# main_board.net
KiCad netlist of a schematic drawn in EAGLE
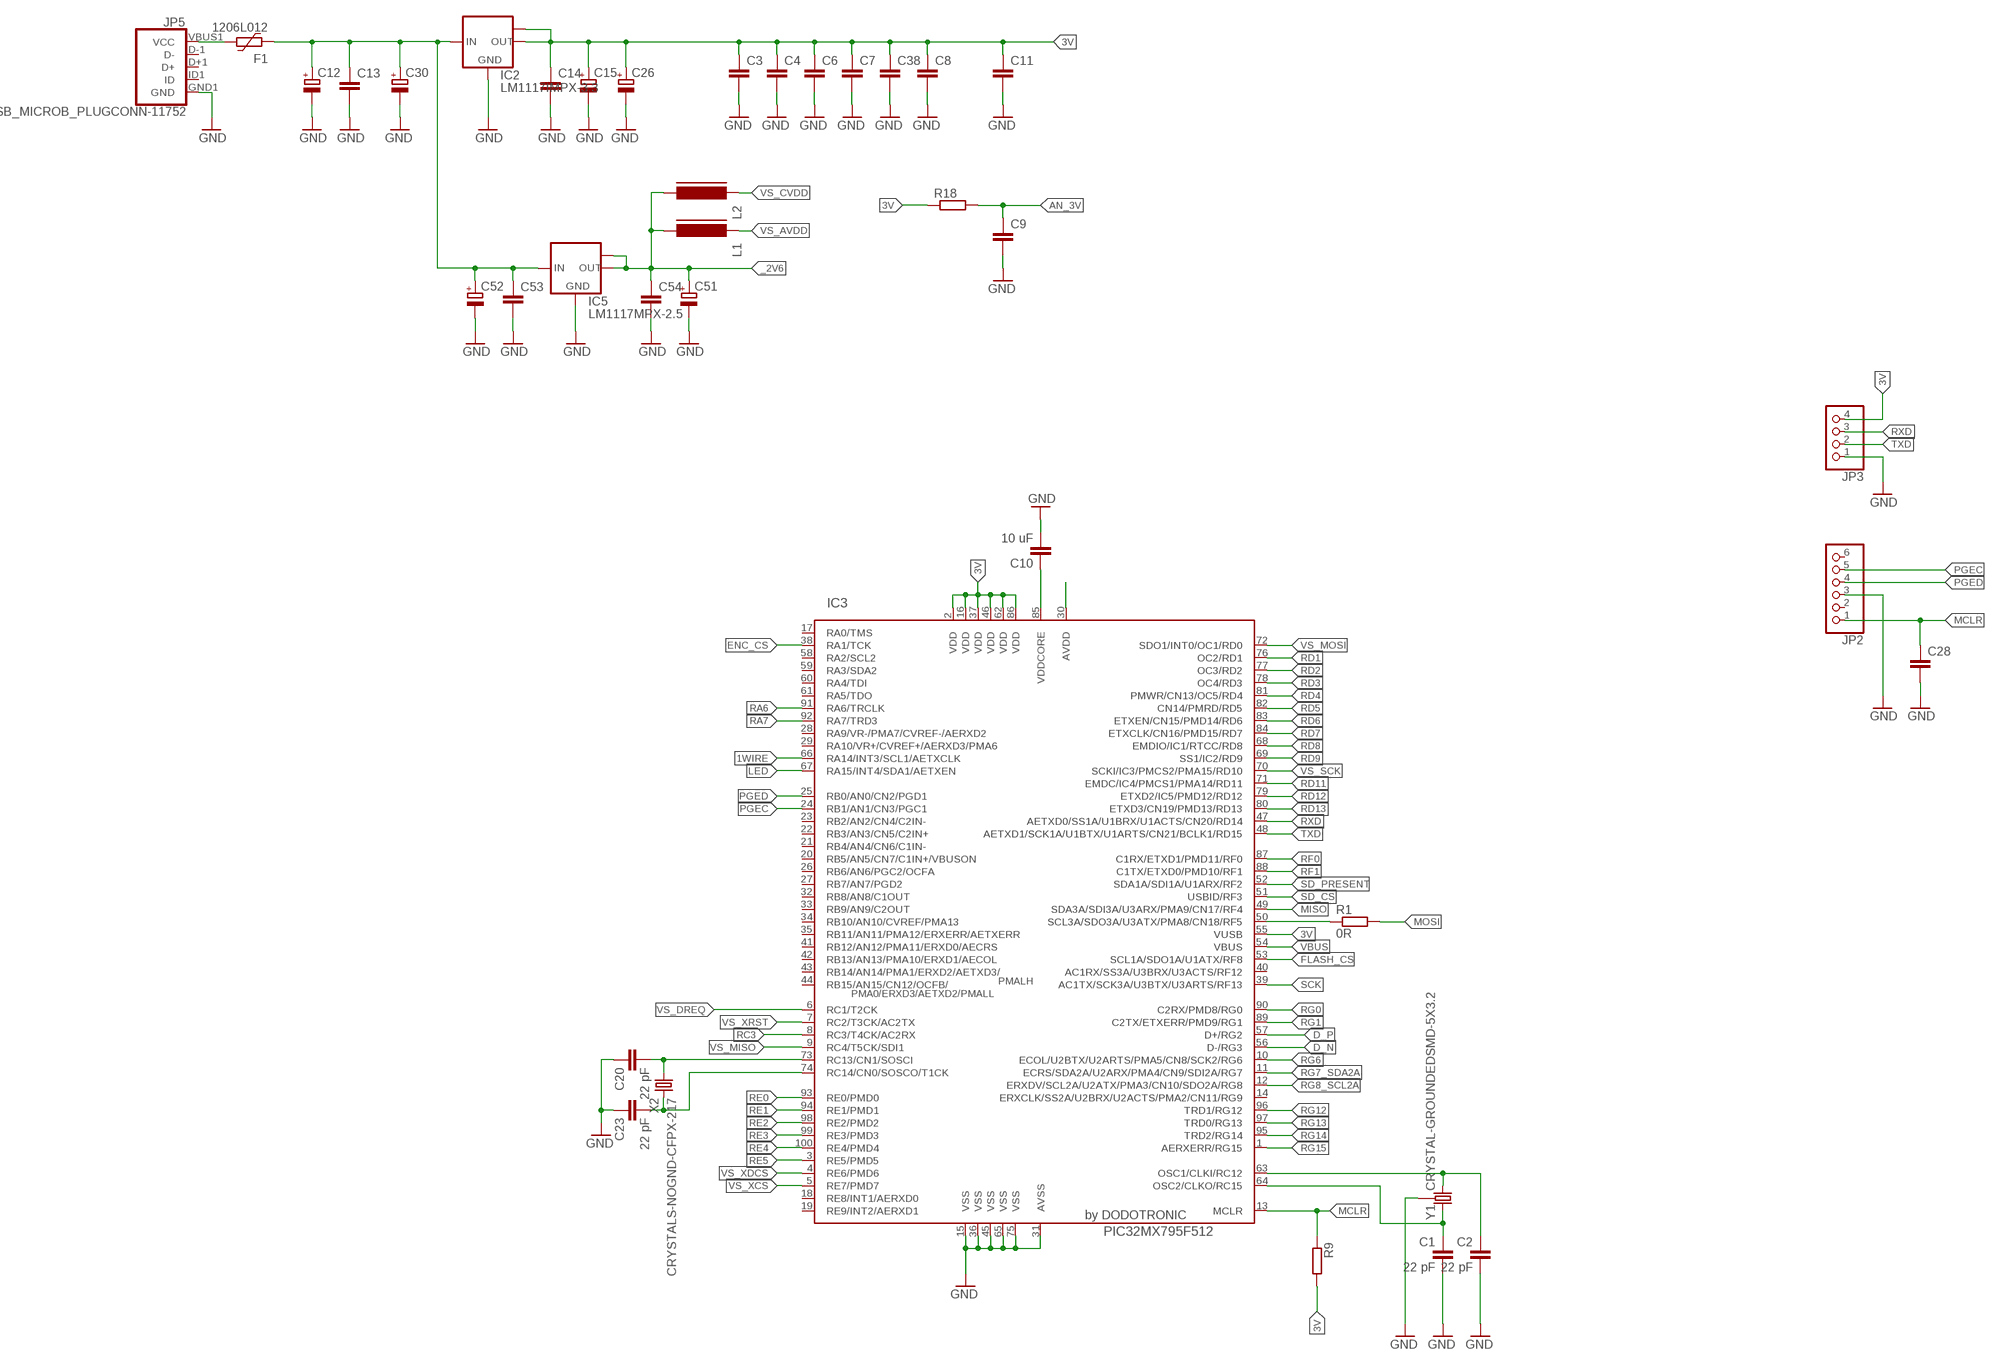
[diagram p0: schematic, sheet 1, part 1 of 3]
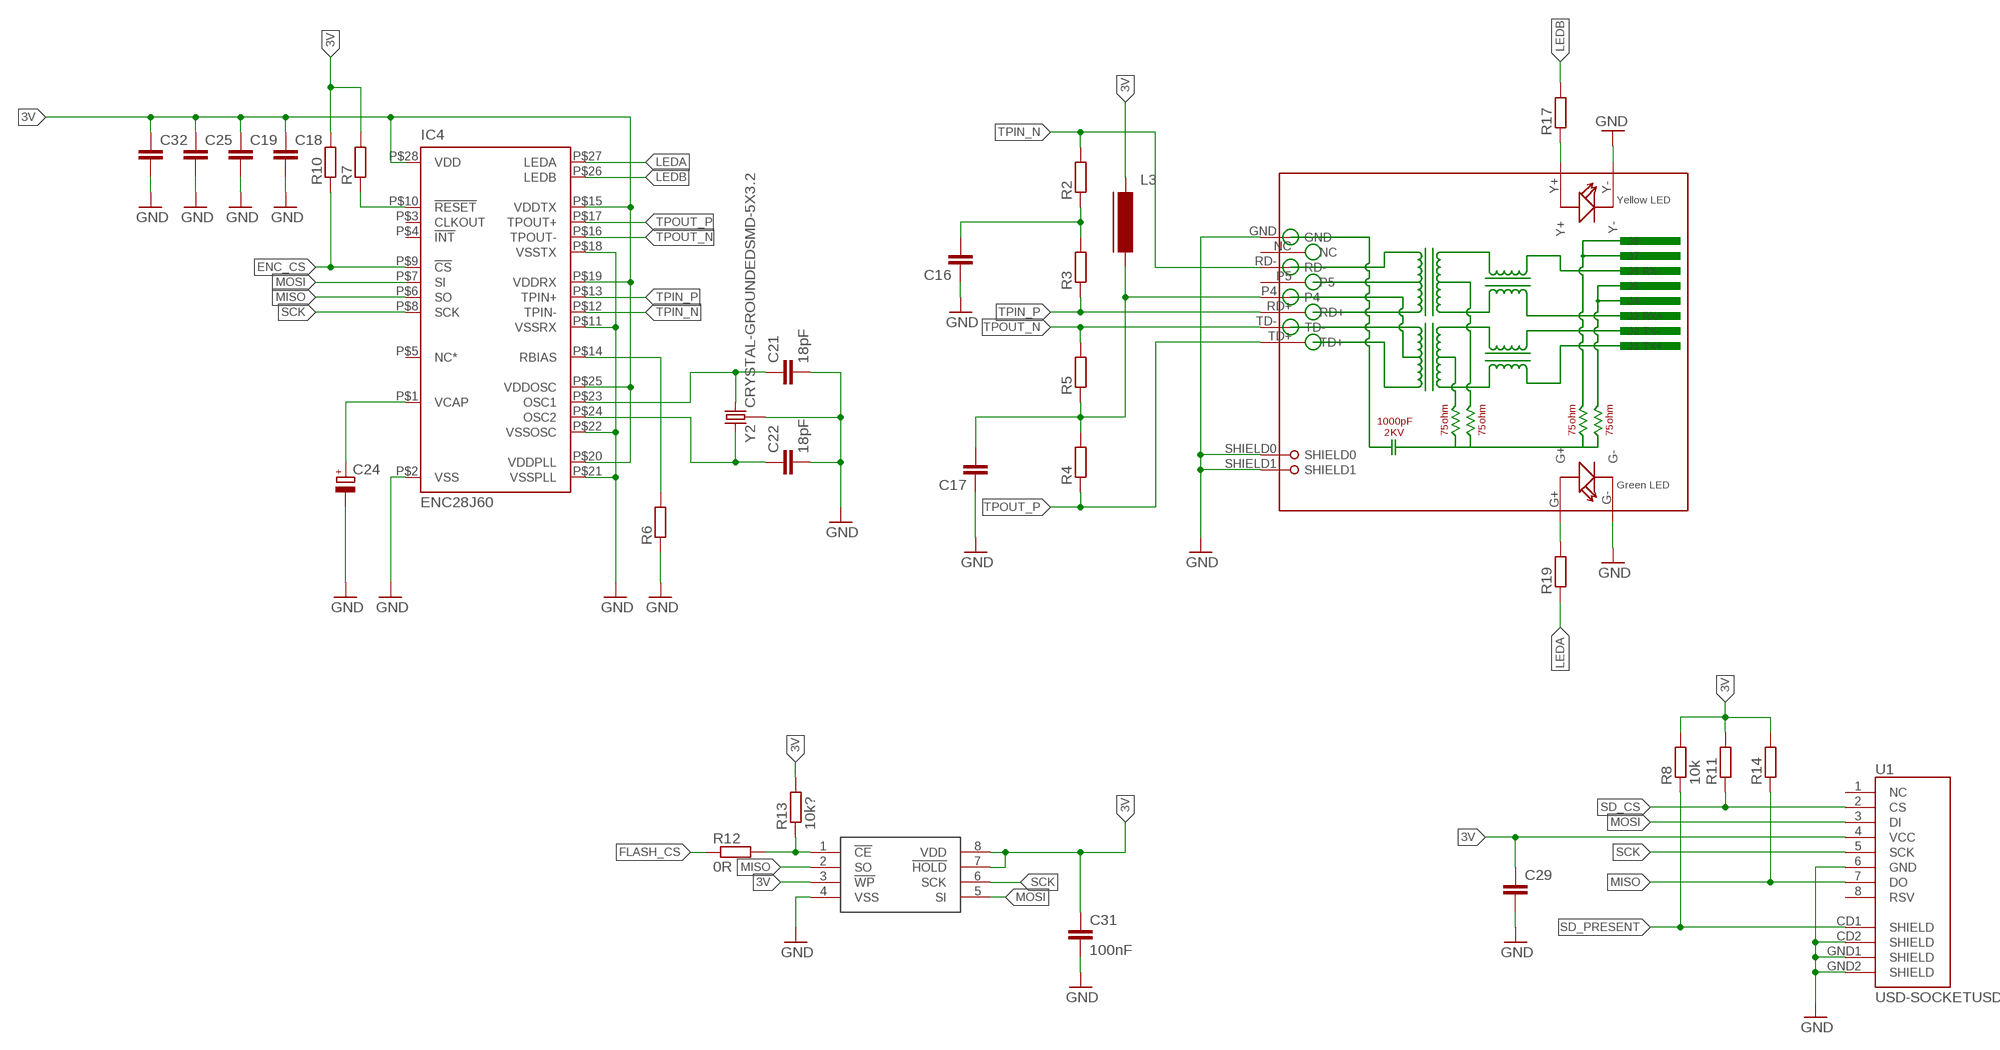
[diagram p1: schematic, sheet 1, part 2 of 3]
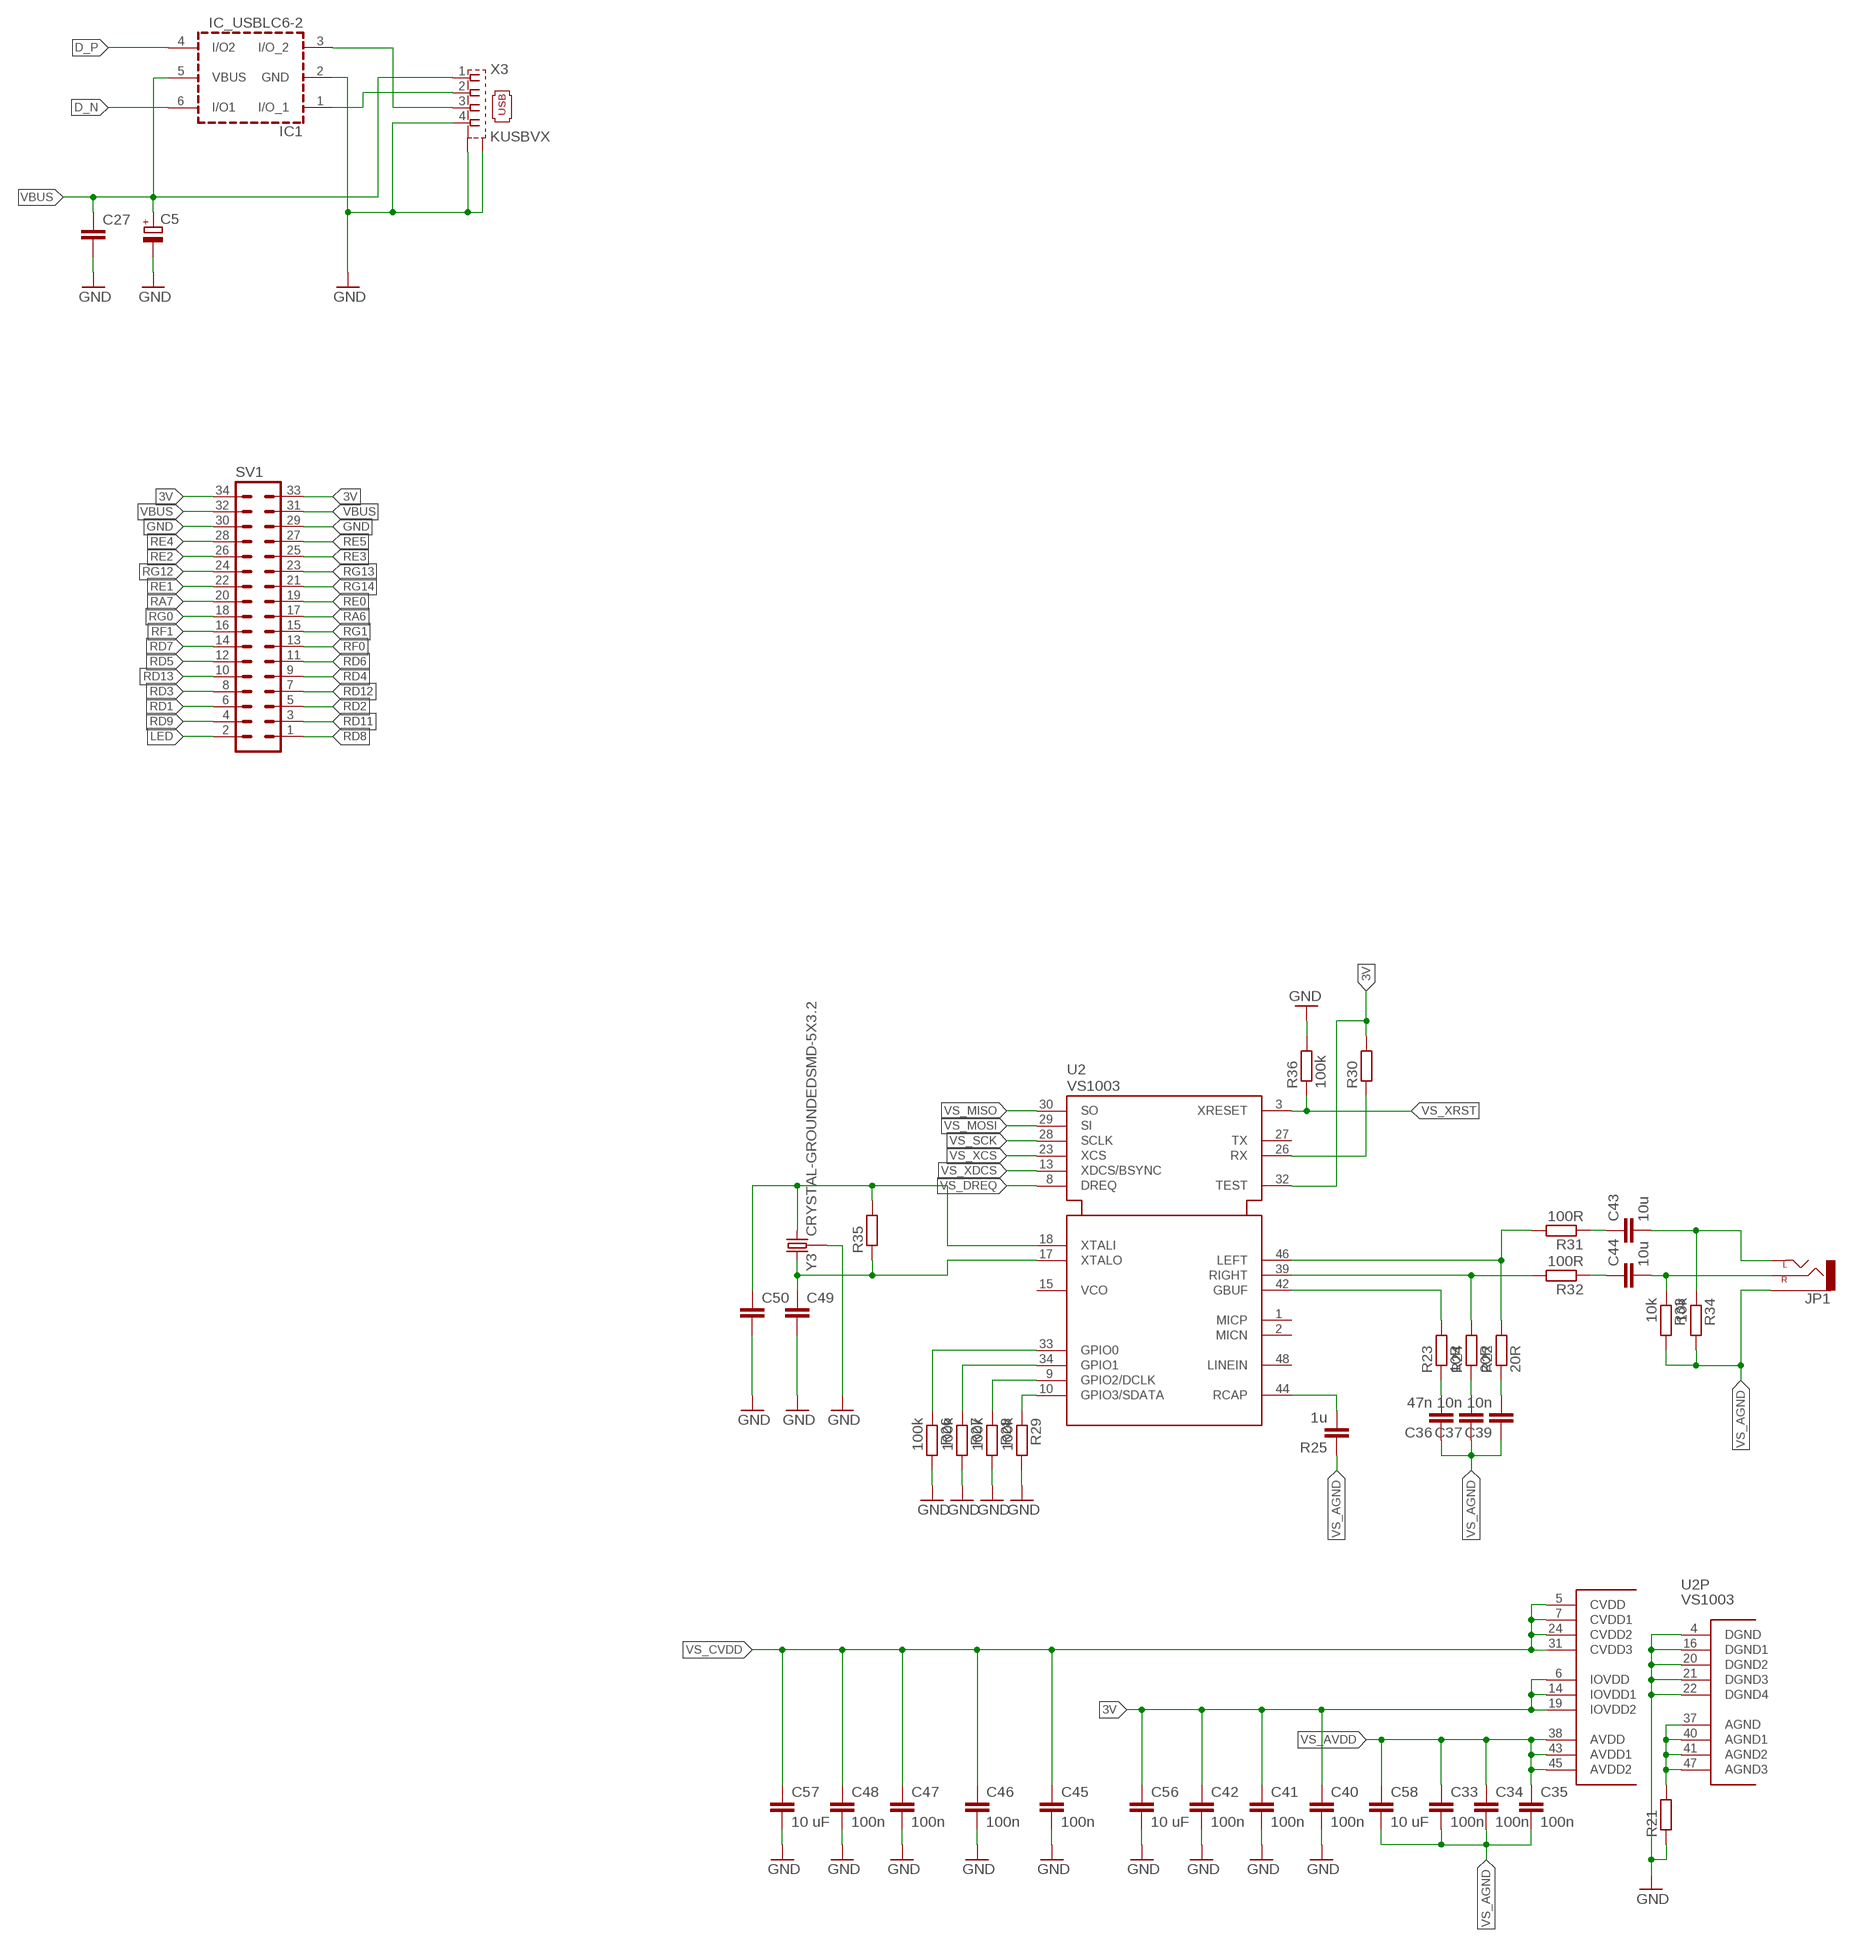
[diagram p2: schematic, sheet 1, part 3 of 3]

(export (version "E")
  (design (tool "Eeschema 10.0.6"))
  (components
    (comp (ref "C1")
      (value "22 pF")
      (footprint "eagle-import:C0603")
      (libsource (lib "eagle-import") (part "C-EUC0603"))
    )
    (comp (ref "C2")
      (value "22 pF")
      (footprint "eagle-import:C0603")
      (libsource (lib "eagle-import") (part "C-EUC0603"))
    )
    (comp (ref "C3")
      (value "C-EUC0402")
      (footprint "eagle-import:C0402")
      (libsource (lib "eagle-import") (part "C-EUC0402"))
    )
    (comp (ref "C4")
      (value "C-EUC0402")
      (footprint "eagle-import:C0402")
      (libsource (lib "eagle-import") (part "C-EUC0402"))
    )
    (comp (ref "C5")
      (value "CPOL-EUSMCA")
      (footprint "eagle-import:SMC_A")
      (libsource (lib "eagle-import") (part "CPOL-EUSMCA"))
    )
    (comp (ref "C6")
      (value "C-EUC0402")
      (footprint "eagle-import:C0402")
      (libsource (lib "eagle-import") (part "C-EUC0402"))
    )
    (comp (ref "C7")
      (value "C-EUC0402")
      (footprint "eagle-import:C0402")
      (libsource (lib "eagle-import") (part "C-EUC0402"))
    )
    (comp (ref "C8")
      (value "C-EUC0402")
      (footprint "eagle-import:C0402")
      (libsource (lib "eagle-import") (part "C-EUC0402"))
    )
    (comp (ref "C9")
      (value "C-EUC0402")
      (footprint "eagle-import:C0402")
      (libsource (lib "eagle-import") (part "C-EUC0402"))
    )
    (comp (ref "C10")
      (value "10 uF")
      (footprint "eagle-import:C0603")
      (libsource (lib "eagle-import") (part "C-EUC0603"))
    )
    (comp (ref "C11")
      (value "C-EUC0402")
      (footprint "eagle-import:C0402")
      (libsource (lib "eagle-import") (part "C-EUC0402"))
    )
    (comp (ref "C12")
      (value "CPOL-EUSMCB")
      (footprint "eagle-import:SMC_B")
      (libsource (lib "eagle-import") (part "CPOL-EUSMCB"))
    )
    (comp (ref "C13")
      (value "C-EUC0603")
      (footprint "eagle-import:C0603")
      (libsource (lib "eagle-import") (part "C-EUC0603"))
    )
    (comp (ref "C14")
      (value "C-EUC0603")
      (footprint "eagle-import:C0603")
      (libsource (lib "eagle-import") (part "C-EUC0603"))
    )
    (comp (ref "C15")
      (value "CPOL-EUSMCB")
      (footprint "eagle-import:SMC_B")
      (libsource (lib "eagle-import") (part "CPOL-EUSMCB"))
    )
    (comp (ref "C16")
      (value "C-EUC0603")
      (footprint "eagle-import:C0603")
      (libsource (lib "eagle-import") (part "C-EUC0603"))
    )
    (comp (ref "C17")
      (value "C-EUC0603")
      (footprint "eagle-import:C0603")
      (libsource (lib "eagle-import") (part "C-EUC0603"))
    )
    (comp (ref "C18")
      (value "C-EUC0402")
      (footprint "eagle-import:C0402")
      (libsource (lib "eagle-import") (part "C-EUC0402"))
    )
    (comp (ref "C19")
      (value "C-EUC0603")
      (footprint "eagle-import:C0603")
      (libsource (lib "eagle-import") (part "C-EUC0603"))
    )
    (comp (ref "C20")
      (value "22 pF")
      (footprint "eagle-import:C0603")
      (libsource (lib "eagle-import") (part "C-EUC0603"))
    )
    (comp (ref "C21")
      (value "18pF")
      (footprint "eagle-import:C0603")
      (libsource (lib "eagle-import") (part "C-EUC0603"))
    )
    (comp (ref "C22")
      (value "18pF")
      (footprint "eagle-import:C0603")
      (libsource (lib "eagle-import") (part "C-EUC0603"))
    )
    (comp (ref "C23")
      (value "22 pF")
      (footprint "eagle-import:C0603")
      (libsource (lib "eagle-import") (part "C-EUC0603"))
    )
    (comp (ref "C24")
      (value "CPOL-EUSMCA")
      (footprint "eagle-import:SMC_A")
      (libsource (lib "eagle-import") (part "CPOL-EUSMCA"))
    )
    (comp (ref "C25")
      (value "C-EUC0603")
      (footprint "eagle-import:C0603")
      (libsource (lib "eagle-import") (part "C-EUC0603"))
    )
    (comp (ref "C26")
      (value "CPOL-EUSMCA")
      (footprint "eagle-import:SMC_A")
      (libsource (lib "eagle-import") (part "CPOL-EUSMCA"))
    )
    (comp (ref "C27")
      (value "C-EUC0603")
      (footprint "eagle-import:C0603")
      (libsource (lib "eagle-import") (part "C-EUC0603"))
    )
    (comp (ref "C28")
      (value "C-EUC0603")
      (footprint "eagle-import:C0603")
      (libsource (lib "eagle-import") (part "C-EUC0603"))
    )
    (comp (ref "C29")
      (value "C-EUC0603")
      (footprint "eagle-import:C0603")
      (libsource (lib "eagle-import") (part "C-EUC0603"))
    )
    (comp (ref "C30")
      (value "CPOL-EUSMCA")
      (footprint "eagle-import:SMC_A")
      (libsource (lib "eagle-import") (part "CPOL-EUSMCA"))
    )
    (comp (ref "C31")
      (value "100nF")
      (footprint "eagle-import:C0603")
      (libsource (lib "eagle-import") (part "C-EUC0603"))
    )
    (comp (ref "C32")
      (value "C-EUC0402")
      (footprint "eagle-import:C0402")
      (libsource (lib "eagle-import") (part "C-EUC0402"))
    )
    (comp (ref "C33")
      (value "100n")
      (footprint "eagle-import:C0603")
      (libsource (lib "eagle-import") (part "C-EUC0603"))
    )
    (comp (ref "C34")
      (value "100n")
      (footprint "eagle-import:C0603")
      (libsource (lib "eagle-import") (part "C-EUC0603"))
    )
    (comp (ref "C35")
      (value "100n")
      (footprint "eagle-import:C0603")
      (libsource (lib "eagle-import") (part "C-EUC0603"))
    )
    (comp (ref "C36")
      (value "47n")
      (footprint "eagle-import:C0603")
      (libsource (lib "eagle-import") (part "C-EUC0603"))
    )
    (comp (ref "C37")
      (value "10n")
      (footprint "eagle-import:C0603")
      (libsource (lib "eagle-import") (part "C-EUC0603"))
    )
    (comp (ref "C38")
      (value "C-EUC0402")
      (footprint "eagle-import:C0402")
      (libsource (lib "eagle-import") (part "C-EUC0402"))
    )
    (comp (ref "C39")
      (value "10n")
      (footprint "eagle-import:C0603")
      (libsource (lib "eagle-import") (part "C-EUC0603"))
    )
    (comp (ref "C40")
      (value "100n")
      (footprint "eagle-import:C0402")
      (libsource (lib "eagle-import") (part "C-EUC0402"))
    )
    (comp (ref "C41")
      (value "100n")
      (footprint "eagle-import:C0402")
      (libsource (lib "eagle-import") (part "C-EUC0402"))
    )
    (comp (ref "C42")
      (value "100n")
      (footprint "eagle-import:C0402")
      (libsource (lib "eagle-import") (part "C-EUC0402"))
    )
    (comp (ref "C43")
      (value "10u")
      (footprint "eagle-import:C0603")
      (libsource (lib "eagle-import") (part "C-EUC0603"))
    )
    (comp (ref "C44")
      (value "10u")
      (footprint "eagle-import:C0603")
      (libsource (lib "eagle-import") (part "C-EUC0603"))
    )
    (comp (ref "C45")
      (value "100n")
      (footprint "eagle-import:C0402")
      (libsource (lib "eagle-import") (part "C-EUC0402"))
    )
    (comp (ref "C46")
      (value "100n")
      (footprint "eagle-import:C0603")
      (libsource (lib "eagle-import") (part "C-EUC0603"))
    )
    (comp (ref "C47")
      (value "100n")
      (footprint "eagle-import:C0603")
      (libsource (lib "eagle-import") (part "C-EUC0603"))
    )
    (comp (ref "C48")
      (value "100n")
      (footprint "eagle-import:C0603")
      (libsource (lib "eagle-import") (part "C-EUC0603"))
    )
    (comp (ref "C49")
      (value "C-EUC0603")
      (footprint "eagle-import:C0603")
      (libsource (lib "eagle-import") (part "C-EUC0603"))
    )
    (comp (ref "C50")
      (value "C-EUC0603")
      (footprint "eagle-import:C0603")
      (libsource (lib "eagle-import") (part "C-EUC0603"))
    )
    (comp (ref "C51")
      (value "CPOL-EUSMCB")
      (footprint "eagle-import:SMC_B")
      (libsource (lib "eagle-import") (part "CPOL-EUSMCB"))
    )
    (comp (ref "C52")
      (value "CPOL-EUSMCB")
      (footprint "eagle-import:SMC_B")
      (libsource (lib "eagle-import") (part "CPOL-EUSMCB"))
    )
    (comp (ref "C53")
      (value "C-EUC1206")
      (footprint "eagle-import:C1206")
      (libsource (lib "eagle-import") (part "C-EUC1206"))
    )
    (comp (ref "C54")
      (value "C-EUC1206")
      (footprint "eagle-import:C1206")
      (libsource (lib "eagle-import") (part "C-EUC1206"))
    )
    (comp (ref "C56")
      (value "10 uF")
      (footprint "eagle-import:C0603")
      (libsource (lib "eagle-import") (part "C-EUC0603"))
    )
    (comp (ref "C57")
      (value "10 uF")
      (footprint "eagle-import:C0603")
      (libsource (lib "eagle-import") (part "C-EUC0603"))
    )
    (comp (ref "C58")
      (value "10 uF")
      (footprint "eagle-import:C0603")
      (libsource (lib "eagle-import") (part "C-EUC0603"))
    )
    (comp (ref "F1")
      (value "1206L012")
      (footprint "eagle-import:1206L")
      (fields (field (name "MF") "Littelfuse"))
      (libsource (lib "eagle-import") (part "?1206L012"))
    )
    (comp (ref "IC1")
      (value "IC_USBLC6-2")
      (footprint "eagle-import:SOT-23-6L")
      (libsource (lib "eagle-import") (part "IC_USBLC6-2"))
    )
    (comp (ref "IC2")
      (value "LM1117IMPX-3.3")
      (footprint "eagle-import:SOT223")
      (libsource (lib "eagle-import") (part "LM1117IMPX-3.3"))
    )
    (comp (ref "IC3")
      (value "PIC32MX795F512")
      (footprint "eagle-import:TQFP100_12X12")
      (libsource (lib "eagle-import") (part "PIC32MX795F512"))
    )
    (comp (ref "IC4")
      (value "ENC28J60")
      (footprint "eagle-import:TSSOP28W")
      (libsource (lib "eagle-import") (part "ENC28J60"))
    )
    (comp (ref "IC5")
      (value "LM1117MPX-2.5")
      (footprint "eagle-import:SOT223")
      (libsource (lib "eagle-import") (part "LM1117MPX-2.5"))
    )
    (comp (ref "JP1")
      (value "AUDIO-JACKAUDIO_JACK2")
      (footprint "eagle-import:AUDIO-JACK2")
      (libsource (lib "eagle-import") (part "AUDIO-JACKAUDIO_JACK2"))
    )
    (comp (ref "JP2")
      (value "PINHD-1X6")
      (footprint "eagle-import:1X06")
      (libsource (lib "eagle-import") (part "PINHD-1X6"))
    )
    (comp (ref "JP3")
      (value "PINHD-1X4")
      (footprint "eagle-import:1X04")
      (libsource (lib "eagle-import") (part "PINHD-1X4"))
    )
    (comp (ref "JP5")
      (value "USB_MICROB_PLUGCONN-11752")
      (footprint "eagle-import:USB-B-MICRO-SMD_V03")
      (libsource (lib "eagle-import") (part "USB_MICROB_PLUGCONN-11752"))
    )
    (comp (ref "L1")
      (value "FERRITE-0805")
      (footprint "eagle-import:FB805")
      (libsource (lib "eagle-import") (part "FERRITE-0805"))
    )
    (comp (ref "L2")
      (value "FERRITE-0805")
      (footprint "eagle-import:FB805")
      (libsource (lib "eagle-import") (part "FERRITE-0805"))
    )
    (comp (ref "L3")
      (value "FERRITE-0805")
      (footprint "eagle-import:FB805")
      (libsource (lib "eagle-import") (part "FERRITE-0805"))
    )
    (comp (ref "R1")
      (value "0R")
      (footprint "eagle-import:R0603")
      (libsource (lib "eagle-import") (part "R-EU_R0603"))
    )
    (comp (ref "R2")
      (value "R-EU_R0603")
      (footprint "eagle-import:R0603")
      (libsource (lib "eagle-import") (part "R-EU_R0603"))
    )
    (comp (ref "R3")
      (value "R-EU_R0603")
      (footprint "eagle-import:R0603")
      (libsource (lib "eagle-import") (part "R-EU_R0603"))
    )
    (comp (ref "R4")
      (value "R-EU_R0603")
      (footprint "eagle-import:R0603")
      (libsource (lib "eagle-import") (part "R-EU_R0603"))
    )
    (comp (ref "R5")
      (value "R-EU_R0603")
      (footprint "eagle-import:R0603")
      (libsource (lib "eagle-import") (part "R-EU_R0603"))
    )
    (comp (ref "R6")
      (value "R-EU_R0805")
      (footprint "eagle-import:R0805")
      (libsource (lib "eagle-import") (part "R-EU_R0805"))
    )
    (comp (ref "R7")
      (value "R-EU_R0402")
      (footprint "eagle-import:R0402")
      (libsource (lib "eagle-import") (part "R-EU_R0402"))
    )
    (comp (ref "R8")
      (value "10k")
      (footprint "eagle-import:R0603")
      (libsource (lib "eagle-import") (part "R-EU_R0603"))
    )
    (comp (ref "R9")
      (value "R-EU_R0603")
      (footprint "eagle-import:R0603")
      (libsource (lib "eagle-import") (part "R-EU_R0603"))
    )
    (comp (ref "R10")
      (value "R-EU_R0603")
      (footprint "eagle-import:R0603")
      (libsource (lib "eagle-import") (part "R-EU_R0603"))
    )
    (comp (ref "R11")
      (value "R-EU_R0603")
      (footprint "eagle-import:R0603")
      (libsource (lib "eagle-import") (part "R-EU_R0603"))
    )
    (comp (ref "R12")
      (value "0R")
      (footprint "eagle-import:R0603")
      (libsource (lib "eagle-import") (part "R-EU_R0603"))
    )
    (comp (ref "R13")
      (value "10k?")
      (footprint "eagle-import:R0603")
      (libsource (lib "eagle-import") (part "R-EU_R0603"))
    )
    (comp (ref "R14")
      (value "R-EU_R0603")
      (footprint "eagle-import:R0603")
      (libsource (lib "eagle-import") (part "R-EU_R0603"))
    )
    (comp (ref "R17")
      (value "R-EU_R1206")
      (footprint "eagle-import:R1206")
      (libsource (lib "eagle-import") (part "R-EU_R1206"))
    )
    (comp (ref "R18")
      (value "R-EU_R0805")
      (footprint "eagle-import:R0805")
      (libsource (lib "eagle-import") (part "R-EU_R0805"))
    )
    (comp (ref "R19")
      (value "R-EU_R1206")
      (footprint "eagle-import:R1206")
      (libsource (lib "eagle-import") (part "R-EU_R1206"))
    )
    (comp (ref "R21")
      (value "R-EU_R0603")
      (footprint "eagle-import:R0603")
      (libsource (lib "eagle-import") (part "R-EU_R0603"))
    )
    (comp (ref "R22")
      (value "20R")
      (footprint "eagle-import:R0603")
      (libsource (lib "eagle-import") (part "R-EU_R0603"))
    )
    (comp (ref "R23")
      (value "10R")
      (footprint "eagle-import:R0603")
      (libsource (lib "eagle-import") (part "R-EU_R0603"))
    )
    (comp (ref "R24")
      (value "20R")
      (footprint "eagle-import:R0603")
      (libsource (lib "eagle-import") (part "R-EU_R0603"))
    )
    (comp (ref "R25")
      (value "1u")
      (footprint "eagle-import:C0603")
      (libsource (lib "eagle-import") (part "C-EUC0603"))
    )
    (comp (ref "R26")
      (value "100k")
      (footprint "eagle-import:R0402")
      (libsource (lib "eagle-import") (part "R-EU_R0402"))
    )
    (comp (ref "R27")
      (value "100k")
      (footprint "eagle-import:R0402")
      (libsource (lib "eagle-import") (part "R-EU_R0402"))
    )
    (comp (ref "R28")
      (value "100k")
      (footprint "eagle-import:R0402")
      (libsource (lib "eagle-import") (part "R-EU_R0402"))
    )
    (comp (ref "R29")
      (value "100k")
      (footprint "eagle-import:R0402")
      (libsource (lib "eagle-import") (part "R-EU_R0402"))
    )
    (comp (ref "R30")
      (value "R-EU_0204/7")
      (footprint "eagle-import:0204_7")
      (libsource (lib "eagle-import") (part "R-EU_0204/7"))
    )
    (comp (ref "R31")
      (value "100R")
      (footprint "eagle-import:R0603")
      (libsource (lib "eagle-import") (part "R-EU_R0603"))
    )
    (comp (ref "R32")
      (value "100R")
      (footprint "eagle-import:R0603")
      (libsource (lib "eagle-import") (part "R-EU_R0603"))
    )
    (comp (ref "R33")
      (value "10k")
      (footprint "eagle-import:R0603")
      (libsource (lib "eagle-import") (part "R-EU_R0603"))
    )
    (comp (ref "R34")
      (value "10k")
      (footprint "eagle-import:R0603")
      (libsource (lib "eagle-import") (part "R-EU_R0603"))
    )
    (comp (ref "R35")
      (value "R-EU_R0603")
      (footprint "eagle-import:R0603")
      (libsource (lib "eagle-import") (part "R-EU_R0603"))
    )
    (comp (ref "R36")
      (value "100k")
      (footprint "eagle-import:R0603")
      (libsource (lib "eagle-import") (part "R-EU_R0603"))
    )
    (comp (ref "RJ1")
      (value "HR911105A")
      (footprint "eagle-import:HR911105A")
      (libsource (lib "eagle-import") (part "HR911105A"))
    )
    (comp (ref "SV1")
      (value "ML34L")
      (footprint "eagle-import:ML34L")
      (libsource (lib "eagle-import") (part "ML34L"))
    )
    (comp (ref "U$2")
      (value "SST25VF016BSO8M")
      (footprint "eagle-import:SO-08M")
      (libsource (lib "eagle-import") (part "SST25VF016BSO8M"))
    )
    (comp (ref "U1")
      (value "USD-SOCKETUSD")
      (footprint "eagle-import:USD-SOCKET-PP")
      (libsource (lib "eagle-import") (part "USD-SOCKETUSD"))
    )
    (comp (ref "U2")
      (value "VS1003")
      (footprint "eagle-import:LQFP48")
      (libsource (lib "eagle-import") (part "VS1003"))
    )
    (comp (ref "X2")
      (value "CRYSTALS-NOGND-CFPX-217")
      (footprint "eagle-import:3.2X1.5-2-PAD")
      (libsource (lib "eagle-import") (part "CRYSTALS-NOGND-CFPX-217"))
    )
    (comp (ref "X3")
      (value "KUSBVX")
      (footprint "eagle-import:KUSBVX")
      (libsource (lib "eagle-import") (part "KUSBVX"))
    )
    (comp (ref "Y1")
      (value "CRYSTAL-GROUNDEDSMD-5X3.2")
      (footprint "eagle-import:CRYSTAL-SMD-5X3.2-4PAD")
      (libsource (lib "eagle-import") (part "CRYSTAL-GROUNDEDSMD-5X3.2"))
    )
    (comp (ref "Y2")
      (value "CRYSTAL-GROUNDEDSMD-5X3.2")
      (footprint "eagle-import:CRYSTAL-SMD-5X3.2-4PAD")
      (libsource (lib "eagle-import") (part "CRYSTAL-GROUNDEDSMD-5X3.2"))
    )
    (comp (ref "Y3")
      (value "CRYSTAL-GROUNDEDSMD-5X3.2")
      (footprint "eagle-import:CRYSTAL-SMD-5X3.2-4PAD")
      (libsource (lib "eagle-import") (part "CRYSTAL-GROUNDEDSMD-5X3.2"))
    )
  )
  (nets
    (net (code "1") (name "1WIRE") (class "Default")
      (node (ref "IC3") (pin "66") (pinfunction "RA14/INT3/SCL1/AETXCLK_66") (pintype "bidirectional"))
    )
    (net (code "2") (name "3V") (class "Default")
      (node (ref "C11") (pin "1") (pinfunction "1_1") (pintype "passive"))
      (node (ref "C14") (pin "1") (pinfunction "1_1") (pintype "passive"))
      (node (ref "C15") (pin "+") (pinfunction "+_+") (pintype "passive"))
      (node (ref "C18") (pin "1") (pinfunction "1_1") (pintype "passive"))
      (node (ref "C19") (pin "1") (pinfunction "1_1") (pintype "passive"))
      (node (ref "C25") (pin "1") (pinfunction "1_1") (pintype "passive"))
      (node (ref "C26") (pin "+") (pinfunction "+_+") (pintype "passive"))
      (node (ref "C29") (pin "1") (pinfunction "1_1") (pintype "passive"))
      (node (ref "C3") (pin "1") (pinfunction "1_1") (pintype "passive"))
      (node (ref "C31") (pin "1") (pinfunction "1_1") (pintype "passive"))
      (node (ref "C32") (pin "1") (pinfunction "1_1") (pintype "passive"))
      (node (ref "C38") (pin "1") (pinfunction "1_1") (pintype "passive"))
      (node (ref "C4") (pin "1") (pinfunction "1_1") (pintype "passive"))
      (node (ref "C40") (pin "1") (pinfunction "1_1") (pintype "passive"))
      (node (ref "C41") (pin "1") (pinfunction "1_1") (pintype "passive"))
      (node (ref "C42") (pin "1") (pinfunction "1_1") (pintype "passive"))
      (node (ref "C56") (pin "1") (pinfunction "1_1") (pintype "passive"))
      (node (ref "C6") (pin "1") (pinfunction "1_1") (pintype "passive"))
      (node (ref "C7") (pin "1") (pinfunction "1_1") (pintype "passive"))
      (node (ref "C8") (pin "1") (pinfunction "1_1") (pintype "passive"))
      (node (ref "IC2") (pin "2") (pinfunction "OUT_2") (pintype "passive"))
      (node (ref "IC2") (pin "TAB") (pinfunction "OUT1_TAB") (pintype "passive"))
      (node (ref "IC3") (pin "16") (pinfunction "VDD_16") (pintype "power_in"))
      (node (ref "IC3") (pin "2") (pinfunction "VDD_2") (pintype "power_in"))
      (node (ref "IC3") (pin "37") (pinfunction "VDD_37") (pintype "power_in"))
      (node (ref "IC3") (pin "46") (pinfunction "VDD_46") (pintype "power_in"))
      (node (ref "IC3") (pin "55") (pinfunction "VUSB_55") (pintype "bidirectional"))
      (node (ref "IC3") (pin "62") (pinfunction "VDD_62") (pintype "power_in"))
      (node (ref "IC3") (pin "86") (pinfunction "VDD_86") (pintype "power_in"))
      (node (ref "IC4") (pin "P$15") (pinfunction "VDDTX_P$15") (pintype "input"))
      (node (ref "IC4") (pin "P$19") (pinfunction "VDDRX_P$19") (pintype "input"))
      (node (ref "IC4") (pin "P$20") (pinfunction "VDDPLL_P$20") (pintype "input"))
      (node (ref "IC4") (pin "P$25") (pinfunction "VDDOSC_P$25") (pintype "input"))
      (node (ref "IC4") (pin "P$28") (pinfunction "VDD_P$28") (pintype "input"))
      (node (ref "JP3") (pin "4") (pinfunction "4_4") (pintype "passive"))
      (node (ref "L3") (pin "1") (pinfunction "1_1") (pintype "passive"))
      (node (ref "R10") (pin "2") (pinfunction "2_2") (pintype "passive"))
      (node (ref "R11") (pin "2") (pinfunction "2_2") (pintype "passive"))
      (node (ref "R13") (pin "2") (pinfunction "2_2") (pintype "passive"))
      (node (ref "R14") (pin "2") (pinfunction "2_2") (pintype "passive"))
      (node (ref "R18") (pin "1") (pinfunction "1_1") (pintype "passive"))
      (node (ref "R30") (pin "2") (pinfunction "2_2") (pintype "passive"))
      (node (ref "R7") (pin "2") (pinfunction "2_2") (pintype "passive"))
      (node (ref "R8") (pin "2") (pinfunction "2_2") (pintype "passive"))
      (node (ref "R9") (pin "2") (pinfunction "2_2") (pintype "passive"))
      (node (ref "SV1") (pin "33") (pinfunction "33_33") (pintype "passive"))
      (node (ref "SV1") (pin "34") (pinfunction "34_34") (pintype "passive"))
      (node (ref "U$2") (pin "3") (pinfunction "~{WP}_3") (pintype "bidirectional"))
      (node (ref "U$2") (pin "7") (pinfunction "~{HOLD}_7") (pintype "bidirectional"))
      (node (ref "U$2") (pin "8") (pinfunction "VDD_8") (pintype "bidirectional"))
      (node (ref "U1") (pin "4") (pinfunction "VCC_4") (pintype "bidirectional"))
      (node (ref "U2") (pin "14") (pinfunction "IOVDD1_14") (pintype "power_in"))
      (node (ref "U2") (pin "19") (pinfunction "IOVDD2_19") (pintype "power_in"))
      (node (ref "U2") (pin "32") (pinfunction "TEST_32") (pintype "bidirectional"))
      (node (ref "U2") (pin "6") (pinfunction "IOVDD_6") (pintype "power_in"))
    )
    (net (code "3") (name "AN_3V") (class "Default")
      (node (ref "C9") (pin "1") (pinfunction "1_1") (pintype "passive"))
      (node (ref "IC3") (pin "30") (pinfunction "AVDD_30") (pintype "bidirectional"))
      (node (ref "R18") (pin "2") (pinfunction "2_2") (pintype "passive"))
    )
    (net (code "4") (name "D_N") (class "Default")
      (node (ref "IC1") (pin "6") (pinfunction "I/O1_6") (pintype "bidirectional"))
      (node (ref "IC3") (pin "56") (pinfunction "D-/RG3_56") (pintype "bidirectional"))
    )
    (net (code "5") (name "D_P") (class "Default")
      (node (ref "IC1") (pin "4") (pinfunction "I/O2_4") (pintype "bidirectional"))
      (node (ref "IC3") (pin "57") (pinfunction "D+/RG2_57") (pintype "bidirectional"))
    )
    (net (code "6") (name "ENC_CS") (class "Default")
      (node (ref "IC3") (pin "38") (pinfunction "RA1/TCK_38") (pintype "bidirectional"))
      (node (ref "IC4") (pin "P$9") (pinfunction "~{CS}_P$9") (pintype "input"))
      (node (ref "R10") (pin "1") (pinfunction "1_1") (pintype "passive"))
    )
    (net (code "7") (name "FLASH_CS") (class "Default")
      (node (ref "IC3") (pin "53") (pinfunction "SCL1A/SDO1A/U1ATX/RF8_53") (pintype "bidirectional"))
      (node (ref "R12") (pin "1") (pinfunction "1_1") (pintype "passive"))
    )
    (net (code "8") (name "GND") (class "Default")
      (node (ref "C1") (pin "2") (pinfunction "2_2") (pintype "passive"))
      (node (ref "C10") (pin "2") (pinfunction "2_2") (pintype "passive"))
      (node (ref "C11") (pin "2") (pinfunction "2_2") (pintype "passive"))
      (node (ref "C12") (pin "-") (pinfunction "-_-") (pintype "passive"))
      (node (ref "C13") (pin "2") (pinfunction "2_2") (pintype "passive"))
      (node (ref "C14") (pin "2") (pinfunction "2_2") (pintype "passive"))
      (node (ref "C15") (pin "-") (pinfunction "-_-") (pintype "passive"))
      (node (ref "C16") (pin "1") (pinfunction "1_1") (pintype "passive"))
      (node (ref "C17") (pin "1") (pinfunction "1_1") (pintype "passive"))
      (node (ref "C18") (pin "2") (pinfunction "2_2") (pintype "passive"))
      (node (ref "C19") (pin "2") (pinfunction "2_2") (pintype "passive"))
      (node (ref "C2") (pin "2") (pinfunction "2_2") (pintype "passive"))
      (node (ref "C20") (pin "1") (pinfunction "1_1") (pintype "passive"))
      (node (ref "C21") (pin "2") (pinfunction "2_2") (pintype "passive"))
      (node (ref "C22") (pin "2") (pinfunction "2_2") (pintype "passive"))
      (node (ref "C23") (pin "1") (pinfunction "1_1") (pintype "passive"))
      (node (ref "C24") (pin "-") (pinfunction "-_-") (pintype "passive"))
      (node (ref "C25") (pin "2") (pinfunction "2_2") (pintype "passive"))
      (node (ref "C26") (pin "-") (pinfunction "-_-") (pintype "passive"))
      (node (ref "C27") (pin "2") (pinfunction "2_2") (pintype "passive"))
      (node (ref "C28") (pin "2") (pinfunction "2_2") (pintype "passive"))
      (node (ref "C29") (pin "2") (pinfunction "2_2") (pintype "passive"))
      (node (ref "C3") (pin "2") (pinfunction "2_2") (pintype "passive"))
      (node (ref "C30") (pin "-") (pinfunction "-_-") (pintype "passive"))
      (node (ref "C31") (pin "2") (pinfunction "2_2") (pintype "passive"))
      (node (ref "C32") (pin "2") (pinfunction "2_2") (pintype "passive"))
      (node (ref "C38") (pin "2") (pinfunction "2_2") (pintype "passive"))
      (node (ref "C4") (pin "2") (pinfunction "2_2") (pintype "passive"))
      (node (ref "C40") (pin "2") (pinfunction "2_2") (pintype "passive"))
      (node (ref "C41") (pin "2") (pinfunction "2_2") (pintype "passive"))
      (node (ref "C42") (pin "2") (pinfunction "2_2") (pintype "passive"))
      (node (ref "C45") (pin "2") (pinfunction "2_2") (pintype "passive"))
      (node (ref "C46") (pin "2") (pinfunction "2_2") (pintype "passive"))
      (node (ref "C47") (pin "2") (pinfunction "2_2") (pintype "passive"))
      (node (ref "C48") (pin "2") (pinfunction "2_2") (pintype "passive"))
      (node (ref "C49") (pin "2") (pinfunction "2_2") (pintype "passive"))
      (node (ref "C5") (pin "-") (pinfunction "-_-") (pintype "passive"))
      (node (ref "C50") (pin "2") (pinfunction "2_2") (pintype "passive"))
      (node (ref "C51") (pin "-") (pinfunction "-_-") (pintype "passive"))
      (node (ref "C52") (pin "-") (pinfunction "-_-") (pintype "passive"))
      (node (ref "C53") (pin "2") (pinfunction "2_2") (pintype "passive"))
      (node (ref "C54") (pin "2") (pinfunction "2_2") (pintype "passive"))
      (node (ref "C56") (pin "2") (pinfunction "2_2") (pintype "passive"))
      (node (ref "C57") (pin "2") (pinfunction "2_2") (pintype "passive"))
      (node (ref "C6") (pin "2") (pinfunction "2_2") (pintype "passive"))
      (node (ref "C7") (pin "2") (pinfunction "2_2") (pintype "passive"))
      (node (ref "C8") (pin "2") (pinfunction "2_2") (pintype "passive"))
      (node (ref "C9") (pin "2") (pinfunction "2_2") (pintype "passive"))
      (node (ref "IC1") (pin "2") (pinfunction "GND_2") (pintype "bidirectional"))
      (node (ref "IC2") (pin "1") (pinfunction "GND_1") (pintype "input"))
      (node (ref "IC3") (pin "15") (pinfunction "VSS_15") (pintype "power_in"))
      (node (ref "IC3") (pin "31") (pinfunction "AVSS_31") (pintype "bidirectional"))
      (node (ref "IC3") (pin "36") (pinfunction "VSS_36") (pintype "power_in"))
      (node (ref "IC3") (pin "45") (pinfunction "VSS_45") (pintype "power_in"))
      (node (ref "IC3") (pin "65") (pinfunction "VSS_65") (pintype "power_in"))
      (node (ref "IC3") (pin "75") (pinfunction "VSS_75") (pintype "power_in"))
      (node (ref "IC4") (pin "P$11") (pinfunction "VSSRX_P$11") (pintype "input"))
      (node (ref "IC4") (pin "P$18") (pinfunction "VSSTX_P$18") (pintype "input"))
      (node (ref "IC4") (pin "P$2") (pinfunction "VSS_P$2") (pintype "input"))
      (node (ref "IC4") (pin "P$21") (pinfunction "VSSPLL_P$21") (pintype "input"))
      (node (ref "IC4") (pin "P$22") (pinfunction "VSSOSC_P$22") (pintype "input"))
      (node (ref "IC5") (pin "1") (pinfunction "GND_1") (pintype "input"))
      (node (ref "JP2") (pin "3") (pinfunction "3_3") (pintype "passive"))
      (node (ref "JP3") (pin "1") (pinfunction "1_1") (pintype "passive"))
      (node (ref "JP5") (pin "GND1") (pinfunction "GND_GND1") (pintype "bidirectional"))
      (node (ref "R21") (pin "1") (pinfunction "1_1") (pintype "passive"))
      (node (ref "R26") (pin "2") (pinfunction "2_2") (pintype "passive"))
      (node (ref "R27") (pin "2") (pinfunction "2_2") (pintype "passive"))
      (node (ref "R28") (pin "2") (pinfunction "2_2") (pintype "passive"))
      (node (ref "R29") (pin "2") (pinfunction "2_2") (pintype "passive"))
      (node (ref "R36") (pin "2") (pinfunction "2_2") (pintype "passive"))
      (node (ref "R6") (pin "1") (pinfunction "1_1") (pintype "passive"))
      (node (ref "RJ1") (pin "G-") (pinfunction "G-_G-") (pintype "bidirectional"))
      (node (ref "RJ1") (pin "GND") (pinfunction "GND_GND") (pintype "bidirectional"))
      (node (ref "RJ1") (pin "SHIELD0") (pinfunction "SHIELD0_SHIELD0") (pintype "bidirectional"))
      (node (ref "RJ1") (pin "SHIELD1") (pinfunction "SHIELD1_SHIELD1") (pintype "bidirectional"))
      (node (ref "RJ1") (pin "Y-") (pinfunction "Y-_Y-") (pintype "bidirectional"))
      (node (ref "SV1") (pin "29") (pinfunction "29_29") (pintype "passive"))
      (node (ref "SV1") (pin "30") (pinfunction "30_30") (pintype "passive"))
      (node (ref "U$2") (pin "4") (pinfunction "VSS_4") (pintype "bidirectional"))
      (node (ref "U1") (pin "6") (pinfunction "GND_6") (pintype "bidirectional"))
      (node (ref "U1") (pin "CD2") (pinfunction "SHIELD_CD2") (pintype "bidirectional"))
      (node (ref "U1") (pin "GND1") (pinfunction "SHIELD_GND1") (pintype "bidirectional"))
      (node (ref "U1") (pin "GND2") (pinfunction "SHIELD_GND2") (pintype "bidirectional"))
      (node (ref "U2") (pin "16") (pinfunction "DGND1_16") (pintype "power_in"))
      (node (ref "U2") (pin "20") (pinfunction "DGND2_20") (pintype "power_in"))
      (node (ref "U2") (pin "21") (pinfunction "DGND3_21") (pintype "power_in"))
      (node (ref "U2") (pin "22") (pinfunction "DGND4_22") (pintype "power_in"))
      (node (ref "U2") (pin "4") (pinfunction "DGND_4") (pintype "power_in"))
      (node (ref "X3") (pin "4") (pinfunction "4_4") (pintype "passive"))
      (node (ref "X3") (pin "M1") (pinfunction "S1_M1") (pintype "passive"))
      (node (ref "X3") (pin "M2") (pinfunction "S2_M2") (pintype "passive"))
      (node (ref "Y1") (pin "2") (pinfunction "3_2") (pintype "passive"))
      (node (ref "Y1") (pin "4") (pinfunction "3_4") (pintype "passive"))
      (node (ref "Y2") (pin "2") (pinfunction "3_2") (pintype "passive"))
      (node (ref "Y2") (pin "4") (pinfunction "3_4") (pintype "passive"))
      (node (ref "Y3") (pin "2") (pinfunction "3_2") (pintype "passive"))
      (node (ref "Y3") (pin "4") (pinfunction "3_4") (pintype "passive"))
    )
    (net (code "9") (name "LED") (class "Default")
      (node (ref "IC3") (pin "67") (pinfunction "RA15/INT4/SDA1/AETXEN_67") (pintype "bidirectional"))
      (node (ref "SV1") (pin "2") (pinfunction "2_2") (pintype "passive"))
    )
    (net (code "10") (name "LEDA") (class "Default")
      (node (ref "IC4") (pin "P$27") (pinfunction "LEDA_P$27") (pintype "output"))
      (node (ref "R19") (pin "1") (pinfunction "1_1") (pintype "passive"))
    )
    (net (code "11") (name "LEDB") (class "Default")
      (node (ref "IC4") (pin "P$26") (pinfunction "LEDB_P$26") (pintype "output"))
      (node (ref "R17") (pin "2") (pinfunction "2_2") (pintype "passive"))
    )
    (net (code "12") (name "MCLR") (class "Default")
      (node (ref "C28") (pin "1") (pinfunction "1_1") (pintype "passive"))
      (node (ref "IC3") (pin "13") (pinfunction "MCLR_13") (pintype "bidirectional"))
      (node (ref "JP2") (pin "1") (pinfunction "1_1") (pintype "passive"))
      (node (ref "R9") (pin "1") (pinfunction "1_1") (pintype "passive"))
    )
    (net (code "13") (name "MISO") (class "Default")
      (node (ref "IC3") (pin "49") (pinfunction "SDA3A/SDI3A/U3ARX/PMA9/CN17/RF4_49") (pintype "bidirectional"))
      (node (ref "IC4") (pin "P$6") (pinfunction "SO_P$6") (pintype "output"))
      (node (ref "R14") (pin "1") (pinfunction "1_1") (pintype "passive"))
      (node (ref "U$2") (pin "2") (pinfunction "SO_2") (pintype "bidirectional"))
      (node (ref "U1") (pin "7") (pinfunction "DO_7") (pintype "bidirectional"))
    )
    (net (code "14") (name "MOSI") (class "Default")
      (node (ref "IC4") (pin "P$7") (pinfunction "SI_P$7") (pintype "input"))
      (node (ref "R1") (pin "2") (pinfunction "2_2") (pintype "passive"))
      (node (ref "U$2") (pin "5") (pinfunction "SI_5") (pintype "bidirectional"))
      (node (ref "U1") (pin "3") (pinfunction "DI_3") (pintype "bidirectional"))
    )
    (net (code "15") (name "Net-(C16-Pad2)") (class "Default")
      (node (ref "C16") (pin "2") (pinfunction "2_2") (pintype "passive"))
      (node (ref "R2") (pin "1") (pinfunction "1_1") (pintype "passive"))
      (node (ref "R3") (pin "2") (pinfunction "2_2") (pintype "passive"))
    )
    (net (code "16") (name "Net-(C17-Pad2)") (class "Default")
      (node (ref "C17") (pin "2") (pinfunction "2_2") (pintype "passive"))
      (node (ref "L3") (pin "2") (pinfunction "2_2") (pintype "passive"))
      (node (ref "R4") (pin "2") (pinfunction "2_2") (pintype "passive"))
      (node (ref "R5") (pin "1") (pinfunction "1_1") (pintype "passive"))
      (node (ref "RJ1") (pin "P4") (pinfunction "P4_P4") (pintype "bidirectional"))
    )
    (net (code "17") (name "Net-(C36-Pad2)") (class "Default")
      (node (ref "C36") (pin "2") (pinfunction "2_2") (pintype "passive"))
      (node (ref "R23") (pin "1") (pinfunction "1_1") (pintype "passive"))
    )
    (net (code "18") (name "Net-(C37-Pad2)") (class "Default")
      (node (ref "C37") (pin "2") (pinfunction "2_2") (pintype "passive"))
      (node (ref "R24") (pin "1") (pinfunction "1_1") (pintype "passive"))
    )
    (net (code "19") (name "Net-(C39-Pad2)") (class "Default")
      (node (ref "C39") (pin "2") (pinfunction "2_2") (pintype "passive"))
      (node (ref "R22") (pin "1") (pinfunction "1_1") (pintype "passive"))
    )
    (net (code "20") (name "Net-(C43-Pad1)") (class "Default")
      (node (ref "C43") (pin "1") (pinfunction "1_1") (pintype "passive"))
      (node (ref "R31") (pin "1") (pinfunction "1_1") (pintype "passive"))
    )
    (net (code "21") (name "Net-(C44-Pad1)") (class "Default")
      (node (ref "C44") (pin "1") (pinfunction "1_1") (pintype "passive"))
      (node (ref "R32") (pin "1") (pinfunction "1_1") (pintype "passive"))
    )
    (net (code "22") (name "Net-(IC1-I{slash}O_1)") (class "Default")
      (node (ref "IC1") (pin "1") (pinfunction "I/O_1_1") (pintype "bidirectional"))
      (node (ref "X3") (pin "2") (pinfunction "2_2") (pintype "passive"))
    )
    (net (code "23") (name "Net-(IC1-I{slash}O_2)") (class "Default")
      (node (ref "IC1") (pin "3") (pinfunction "I/O_2_3") (pintype "bidirectional"))
      (node (ref "X3") (pin "3") (pinfunction "3_3") (pintype "passive"))
    )
    (net (code "24") (name "Net-(IC3-OSC1{slash}CLKI{slash}RC12)") (class "Default")
      (node (ref "C2") (pin "1") (pinfunction "1_1") (pintype "passive"))
      (node (ref "IC3") (pin "63") (pinfunction "OSC1/CLKI/RC12_63") (pintype "bidirectional"))
      (node (ref "Y1") (pin "1") (pinfunction "2_1") (pintype "passive"))
    )
    (net (code "25") (name "Net-(IC3-OSC2{slash}CLKO{slash}RC15)") (class "Default")
      (node (ref "C1") (pin "1") (pinfunction "1_1") (pintype "passive"))
      (node (ref "IC3") (pin "64") (pinfunction "OSC2/CLKO/RC15_64") (pintype "bidirectional"))
      (node (ref "Y1") (pin "3") (pinfunction "1_3") (pintype "passive"))
    )
    (net (code "26") (name "Net-(IC3-RC13{slash}CN1{slash}SOSCI)") (class "Default")
      (node (ref "C20") (pin "2") (pinfunction "2_2") (pintype "passive"))
      (node (ref "IC3") (pin "73") (pinfunction "RC13/CN1/SOSCI_73") (pintype "bidirectional"))
      (node (ref "X2") (pin "1") (pinfunction "1_1") (pintype "passive"))
    )
    (net (code "27") (name "Net-(IC3-RC14{slash}CN0{slash}SOSCO{slash}T1CK)") (class "Default")
      (node (ref "C23") (pin "2") (pinfunction "2_2") (pintype "passive"))
      (node (ref "IC3") (pin "74") (pinfunction "RC14/CN0/SOSCO/T1CK_74") (pintype "bidirectional"))
      (node (ref "X2") (pin "2") (pinfunction "2_2") (pintype "passive"))
    )
    (net (code "28") (name "Net-(IC3-SCL3A{slash}SDO3A{slash}U3ATX{slash}PMA8{slash}CN18{slash}RF5)") (class "Default")
      (node (ref "IC3") (pin "50") (pinfunction "SCL3A/SDO3A/U3ATX/PMA8/CN18/RF5_50") (pintype "bidirectional"))
      (node (ref "R1") (pin "1") (pinfunction "1_1") (pintype "passive"))
    )
    (net (code "29") (name "Net-(IC3-VDDCORE)") (class "Default")
      (node (ref "C10") (pin "1") (pinfunction "1_1") (pintype "passive"))
      (node (ref "IC3") (pin "85") (pinfunction "VDDCORE_85") (pintype "bidirectional"))
    )
    (net (code "30") (name "Net-(IC4-OSC1)") (class "Default")
      (node (ref "C21") (pin "1") (pinfunction "1_1") (pintype "passive"))
      (node (ref "IC4") (pin "P$23") (pinfunction "OSC1_P$23") (pintype "input"))
      (node (ref "Y2") (pin "1") (pinfunction "2_1") (pintype "passive"))
    )
    (net (code "31") (name "Net-(IC4-OSC2)") (class "Default")
      (node (ref "C22") (pin "1") (pinfunction "1_1") (pintype "passive"))
      (node (ref "IC4") (pin "P$24") (pinfunction "OSC2_P$24") (pintype "output"))
      (node (ref "Y2") (pin "3") (pinfunction "1_3") (pintype "passive"))
    )
    (net (code "32") (name "Net-(IC4-RBIAS)") (class "Default")
      (node (ref "IC4") (pin "P$14") (pinfunction "RBIAS_P$14") (pintype "input"))
      (node (ref "R6") (pin "2") (pinfunction "2_2") (pintype "passive"))
    )
    (net (code "33") (name "Net-(IC4-VCAP)") (class "Default")
      (node (ref "C24") (pin "+") (pinfunction "+_+") (pintype "passive"))
      (node (ref "IC4") (pin "P$1") (pinfunction "VCAP_P$1") (pintype "input"))
    )
    (net (code "34") (name "Net-(IC4-~{RESET})") (class "Default")
      (node (ref "IC4") (pin "P$10") (pinfunction "~{RESET}_P$10") (pintype "input"))
      (node (ref "R7") (pin "1") (pinfunction "1_1") (pintype "passive"))
    )
    (net (code "35") (name "Net-(JP1-LEFT)") (class "Default")
      (node (ref "C43") (pin "2") (pinfunction "2_2") (pintype "passive"))
      (node (ref "JP1") (pin "TIP") (pinfunction "LEFT_TIP") (pintype "bidirectional"))
      (node (ref "R34") (pin "1") (pinfunction "1_1") (pintype "passive"))
    )
    (net (code "36") (name "Net-(JP1-RIGHT)") (class "Default")
      (node (ref "C44") (pin "2") (pinfunction "2_2") (pintype "passive"))
      (node (ref "JP1") (pin "RING") (pinfunction "RIGHT_RING") (pintype "bidirectional"))
      (node (ref "R33") (pin "1") (pinfunction "1_1") (pintype "passive"))
    )
    (net (code "37") (name "Net-(JP5-VCC)") (class "Default")
      (node (ref "F1") (pin "1") (pinfunction "1_1") (pintype "passive"))
      (node (ref "JP5") (pin "VBUS1") (pinfunction "VCC_VBUS1") (pintype "bidirectional"))
    )
    (net (code "38") (name "Net-(R17-Pad1)") (class "Default")
      (node (ref "R17") (pin "1") (pinfunction "1_1") (pintype "passive"))
      (node (ref "RJ1") (pin "Y+") (pinfunction "Y+_Y+") (pintype "bidirectional"))
    )
    (net (code "39") (name "Net-(R19-Pad2)") (class "Default")
      (node (ref "R19") (pin "2") (pinfunction "2_2") (pintype "passive"))
      (node (ref "RJ1") (pin "G+") (pinfunction "G+_G+") (pintype "bidirectional"))
    )
    (net (code "40") (name "Net-(U$2-~{CE})") (class "Default")
      (node (ref "R12") (pin "2") (pinfunction "2_2") (pintype "passive"))
      (node (ref "R13") (pin "1") (pinfunction "1_1") (pintype "passive"))
      (node (ref "U$2") (pin "1") (pinfunction "~{CE}_1") (pintype "bidirectional"))
    )
    (net (code "41") (name "Net-(U2A-GBUF)") (class "Default")
      (node (ref "R23") (pin "2") (pinfunction "2_2") (pintype "passive"))
      (node (ref "U2") (pin "42") (pinfunction "GBUF_42") (pintype "bidirectional"))
    )
    (net (code "42") (name "Net-(U2A-GPIO0)") (class "Default")
      (node (ref "R26") (pin "1") (pinfunction "1_1") (pintype "passive"))
      (node (ref "U2") (pin "33") (pinfunction "GPIO0_33") (pintype "bidirectional"))
    )
    (net (code "43") (name "Net-(U2A-GPIO1)") (class "Default")
      (node (ref "R27") (pin "1") (pinfunction "1_1") (pintype "passive"))
      (node (ref "U2") (pin "34") (pinfunction "GPIO1_34") (pintype "bidirectional"))
    )
    (net (code "44") (name "Net-(U2A-GPIO2{slash}DCLK)") (class "Default")
      (node (ref "R28") (pin "1") (pinfunction "1_1") (pintype "passive"))
      (node (ref "U2") (pin "9") (pinfunction "GPIO2/DCLK_9") (pintype "bidirectional"))
    )
    (net (code "45") (name "Net-(U2A-GPIO3{slash}SDATA)") (class "Default")
      (node (ref "R29") (pin "1") (pinfunction "1_1") (pintype "passive"))
      (node (ref "U2") (pin "10") (pinfunction "GPIO3/SDATA_10") (pintype "bidirectional"))
    )
    (net (code "46") (name "Net-(U2A-LEFT)") (class "Default")
      (node (ref "R22") (pin "2") (pinfunction "2_2") (pintype "passive"))
      (node (ref "R31") (pin "2") (pinfunction "2_2") (pintype "passive"))
      (node (ref "U2") (pin "46") (pinfunction "LEFT_46") (pintype "bidirectional"))
    )
    (net (code "47") (name "Net-(U2A-RCAP)") (class "Default")
      (node (ref "R25") (pin "2") (pinfunction "2_2") (pintype "passive"))
      (node (ref "U2") (pin "44") (pinfunction "RCAP_44") (pintype "bidirectional"))
    )
    (net (code "48") (name "Net-(U2A-RIGHT)") (class "Default")
      (node (ref "R24") (pin "2") (pinfunction "2_2") (pintype "passive"))
      (node (ref "R32") (pin "2") (pinfunction "2_2") (pintype "passive"))
      (node (ref "U2") (pin "39") (pinfunction "RIGHT_39") (pintype "bidirectional"))
    )
    (net (code "49") (name "Net-(U2A-RX)") (class "Default")
      (node (ref "R30") (pin "1") (pinfunction "1_1") (pintype "passive"))
      (node (ref "U2") (pin "26") (pinfunction "RX_26") (pintype "bidirectional"))
    )
    (net (code "50") (name "Net-(U2A-XTALI)") (class "Default")
      (node (ref "C50") (pin "1") (pinfunction "1_1") (pintype "passive"))
      (node (ref "R35") (pin "2") (pinfunction "2_2") (pintype "passive"))
      (node (ref "U2") (pin "18") (pinfunction "XTALI_18") (pintype "bidirectional"))
      (node (ref "Y3") (pin "1") (pinfunction "2_1") (pintype "passive"))
    )
    (net (code "51") (name "Net-(U2A-XTALO)") (class "Default")
      (node (ref "C49") (pin "1") (pinfunction "1_1") (pintype "passive"))
      (node (ref "R35") (pin "1") (pinfunction "1_1") (pintype "passive"))
      (node (ref "U2") (pin "17") (pinfunction "XTALO_17") (pintype "bidirectional"))
      (node (ref "Y3") (pin "3") (pinfunction "1_3") (pintype "passive"))
    )
    (net (code "52") (name "PGEC") (class "Default")
      (node (ref "IC3") (pin "24") (pinfunction "RB1/AN1/CN3/PGC1_24") (pintype "bidirectional"))
      (node (ref "JP2") (pin "5") (pinfunction "5_5") (pintype "passive"))
    )
    (net (code "53") (name "PGED") (class "Default")
      (node (ref "IC3") (pin "25") (pinfunction "RB0/AN0/CN2/PGD1_25") (pintype "bidirectional"))
      (node (ref "JP2") (pin "4") (pinfunction "4_4") (pintype "passive"))
    )
    (net (code "54") (name "RA6") (class "Default")
      (node (ref "IC3") (pin "91") (pinfunction "RA6/TRCLK_91") (pintype "bidirectional"))
      (node (ref "SV1") (pin "17") (pinfunction "17_17") (pintype "passive"))
    )
    (net (code "55") (name "RA7") (class "Default")
      (node (ref "IC3") (pin "92") (pinfunction "RA7/TRD3_92") (pintype "bidirectional"))
      (node (ref "SV1") (pin "20") (pinfunction "20_20") (pintype "passive"))
    )
    (net (code "56") (name "RC3") (class "Default")
      (node (ref "IC3") (pin "8") (pinfunction "RC3/T4CK/AC2RX_8") (pintype "bidirectional"))
    )
    (net (code "57") (name "RD1") (class "Default")
      (node (ref "IC3") (pin "76") (pinfunction "OC2/RD1_76") (pintype "bidirectional"))
      (node (ref "SV1") (pin "6") (pinfunction "6_6") (pintype "passive"))
    )
    (net (code "58") (name "RD2") (class "Default")
      (node (ref "IC3") (pin "77") (pinfunction "OC3/RD2_77") (pintype "bidirectional"))
      (node (ref "SV1") (pin "5") (pinfunction "5_5") (pintype "passive"))
    )
    (net (code "59") (name "RD3") (class "Default")
      (node (ref "IC3") (pin "78") (pinfunction "OC4/RD3_78") (pintype "bidirectional"))
      (node (ref "SV1") (pin "8") (pinfunction "8_8") (pintype "passive"))
    )
    (net (code "60") (name "RD4") (class "Default")
      (node (ref "IC3") (pin "81") (pinfunction "PMWR/CN13/OC5/RD4_81") (pintype "bidirectional"))
      (node (ref "SV1") (pin "9") (pinfunction "9_9") (pintype "passive"))
    )
    (net (code "61") (name "RD5") (class "Default")
      (node (ref "IC3") (pin "82") (pinfunction "CN14/PMRD/RD5_82") (pintype "bidirectional"))
      (node (ref "SV1") (pin "12") (pinfunction "12_12") (pintype "passive"))
    )
    (net (code "62") (name "RD6") (class "Default")
      (node (ref "IC3") (pin "83") (pinfunction "ETXEN/CN15/PMD14/RD6_83") (pintype "bidirectional"))
      (node (ref "SV1") (pin "11") (pinfunction "11_11") (pintype "passive"))
    )
    (net (code "63") (name "RD7") (class "Default")
      (node (ref "IC3") (pin "84") (pinfunction "ETXCLK/CN16/PMD15/RD7_84") (pintype "bidirectional"))
      (node (ref "SV1") (pin "14") (pinfunction "14_14") (pintype "passive"))
    )
    (net (code "64") (name "RD8") (class "Default")
      (node (ref "IC3") (pin "68") (pinfunction "EMDIO/IC1/RTCC/RD8_68") (pintype "bidirectional"))
      (node (ref "SV1") (pin "1") (pinfunction "1_1") (pintype "passive"))
    )
    (net (code "65") (name "RD9") (class "Default")
      (node (ref "IC3") (pin "69") (pinfunction "SS1/IC2/RD9_69") (pintype "bidirectional"))
      (node (ref "SV1") (pin "4") (pinfunction "4_4") (pintype "passive"))
    )
    (net (code "66") (name "RD11") (class "Default")
      (node (ref "IC3") (pin "71") (pinfunction "EMDC/IC4/PMCS1/PMA14/RD11_71") (pintype "bidirectional"))
      (node (ref "SV1") (pin "3") (pinfunction "3_3") (pintype "passive"))
    )
    (net (code "67") (name "RD12") (class "Default")
      (node (ref "IC3") (pin "79") (pinfunction "ETXD2/IC5/PMD12/RD12_79") (pintype "bidirectional"))
      (node (ref "SV1") (pin "7") (pinfunction "7_7") (pintype "passive"))
    )
    (net (code "68") (name "RD13") (class "Default")
      (node (ref "IC3") (pin "80") (pinfunction "ETXD3/CN19/PMD13/RD13_80") (pintype "bidirectional"))
      (node (ref "SV1") (pin "10") (pinfunction "10_10") (pintype "passive"))
    )
    (net (code "69") (name "RE0") (class "Default")
      (node (ref "IC3") (pin "93") (pinfunction "RE0/PMD0_93") (pintype "bidirectional"))
      (node (ref "SV1") (pin "19") (pinfunction "19_19") (pintype "passive"))
    )
    (net (code "70") (name "RE1") (class "Default")
      (node (ref "IC3") (pin "94") (pinfunction "RE1/PMD1_94") (pintype "bidirectional"))
      (node (ref "SV1") (pin "22") (pinfunction "22_22") (pintype "passive"))
    )
    (net (code "71") (name "RE2") (class "Default")
      (node (ref "IC3") (pin "98") (pinfunction "RE2/PMD2_98") (pintype "bidirectional"))
      (node (ref "SV1") (pin "26") (pinfunction "26_26") (pintype "passive"))
    )
    (net (code "72") (name "RE3") (class "Default")
      (node (ref "IC3") (pin "99") (pinfunction "RE3/PMD3_99") (pintype "bidirectional"))
      (node (ref "SV1") (pin "25") (pinfunction "25_25") (pintype "passive"))
    )
    (net (code "73") (name "RE4") (class "Default")
      (node (ref "IC3") (pin "100") (pinfunction "RE4/PMD4_100") (pintype "bidirectional"))
      (node (ref "SV1") (pin "28") (pinfunction "28_28") (pintype "passive"))
    )
    (net (code "74") (name "RE5") (class "Default")
      (node (ref "IC3") (pin "3") (pinfunction "RE5/PMD5_3") (pintype "bidirectional"))
      (node (ref "SV1") (pin "27") (pinfunction "27_27") (pintype "passive"))
    )
    (net (code "75") (name "RF0") (class "Default")
      (node (ref "IC3") (pin "87") (pinfunction "C1RX/ETXD1/PMD11/RF0_87") (pintype "bidirectional"))
      (node (ref "SV1") (pin "13") (pinfunction "13_13") (pintype "passive"))
    )
    (net (code "76") (name "RF1") (class "Default")
      (node (ref "IC3") (pin "88") (pinfunction "C1TX/ETXD0/PMD10/RF1_88") (pintype "bidirectional"))
      (node (ref "SV1") (pin "16") (pinfunction "16_16") (pintype "passive"))
    )
    (net (code "77") (name "RG0") (class "Default")
      (node (ref "IC3") (pin "90") (pinfunction "C2RX/PMD8/RG0_90") (pintype "bidirectional"))
      (node (ref "SV1") (pin "18") (pinfunction "18_18") (pintype "passive"))
    )
    (net (code "78") (name "RG1") (class "Default")
      (node (ref "IC3") (pin "89") (pinfunction "C2TX/ETXERR/PMD9/RG1_89") (pintype "bidirectional"))
      (node (ref "SV1") (pin "15") (pinfunction "15_15") (pintype "passive"))
    )
    (net (code "79") (name "RG6") (class "Default")
      (node (ref "IC3") (pin "10") (pinfunction "ECOL/U2BTX/U2ARTS/PMA5/CN8/SCK2/RG6_10") (pintype "bidirectional"))
    )
    (net (code "80") (name "RG7_SDA2A") (class "Default")
      (node (ref "IC3") (pin "11") (pinfunction "ECRS/SDA2A/U2ARX/PMA4/CN9/SDI2A/RG7_11") (pintype "bidirectional"))
    )
    (net (code "81") (name "RG8_SCL2A") (class "Default")
      (node (ref "IC3") (pin "12") (pinfunction "ERXDV/SCL2A/U2ATX/PMA3/CN10/SDO2A/RG8_12") (pintype "bidirectional"))
    )
    (net (code "82") (name "RG12") (class "Default")
      (node (ref "IC3") (pin "96") (pinfunction "TRD1/RG12_96") (pintype "bidirectional"))
      (node (ref "SV1") (pin "24") (pinfunction "24_24") (pintype "passive"))
    )
    (net (code "83") (name "RG13") (class "Default")
      (node (ref "IC3") (pin "97") (pinfunction "TRD0/RG13_97") (pintype "bidirectional"))
      (node (ref "SV1") (pin "23") (pinfunction "23_23") (pintype "passive"))
    )
    (net (code "84") (name "RG14") (class "Default")
      (node (ref "IC3") (pin "95") (pinfunction "TRD2/RG14_95") (pintype "bidirectional"))
      (node (ref "SV1") (pin "21") (pinfunction "21_21") (pintype "passive"))
    )
    (net (code "85") (name "RG15") (class "Default")
      (node (ref "IC3") (pin "1") (pinfunction "AERXERR/RG15_1") (pintype "bidirectional"))
    )
    (net (code "86") (name "RXD") (class "Default")
      (node (ref "IC3") (pin "47") (pinfunction "AETXD0/SS1A/U1BRX/U1ACTS/CN20/RD14_47") (pintype "bidirectional"))
      (node (ref "JP3") (pin "3") (pinfunction "3_3") (pintype "passive"))
    )
    (net (code "87") (name "SCK") (class "Default")
      (node (ref "IC3") (pin "39") (pinfunction "AC1TX/SCK3A/U3BTX/U3ARTS/RF13_39") (pintype "bidirectional"))
      (node (ref "IC4") (pin "P$8") (pinfunction "SCK_P$8") (pintype "input"))
      (node (ref "U$2") (pin "6") (pinfunction "SCK_6") (pintype "bidirectional"))
      (node (ref "U1") (pin "5") (pinfunction "SCK_5") (pintype "bidirectional"))
    )
    (net (code "88") (name "SD_CS") (class "Default")
      (node (ref "IC3") (pin "51") (pinfunction "USBID/RF3_51") (pintype "bidirectional"))
      (node (ref "R11") (pin "1") (pinfunction "1_1") (pintype "passive"))
      (node (ref "U1") (pin "2") (pinfunction "CS_2") (pintype "bidirectional"))
    )
    (net (code "89") (name "SD_PRESENT") (class "Default")
      (node (ref "IC3") (pin "52") (pinfunction "SDA1A/SDI1A/U1ARX/RF2_52") (pintype "bidirectional"))
      (node (ref "R8") (pin "1") (pinfunction "1_1") (pintype "passive"))
      (node (ref "U1") (pin "CD1") (pinfunction "SHIELD_CD1") (pintype "bidirectional"))
    )
    (net (code "90") (name "TPIN_N") (class "Default")
      (node (ref "IC4") (pin "P$12") (pinfunction "TPIN-_P$12") (pintype "input"))
      (node (ref "R2") (pin "2") (pinfunction "2_2") (pintype "passive"))
      (node (ref "RJ1") (pin "RD-") (pinfunction "RD-_RD-") (pintype "bidirectional"))
    )
    (net (code "91") (name "TPIN_P") (class "Default")
      (node (ref "IC4") (pin "P$13") (pinfunction "TPIN+_P$13") (pintype "input"))
      (node (ref "R3") (pin "1") (pinfunction "1_1") (pintype "passive"))
      (node (ref "RJ1") (pin "RD+") (pinfunction "RD+_RD+") (pintype "bidirectional"))
    )
    (net (code "92") (name "TPOUT_N") (class "Default")
      (node (ref "IC4") (pin "P$16") (pinfunction "TPOUT-_P$16") (pintype "output"))
      (node (ref "R5") (pin "2") (pinfunction "2_2") (pintype "passive"))
      (node (ref "RJ1") (pin "TD-") (pinfunction "TD-_TD-") (pintype "bidirectional"))
    )
    (net (code "93") (name "TPOUT_P") (class "Default")
      (node (ref "IC4") (pin "P$17") (pinfunction "TPOUT+_P$17") (pintype "output"))
      (node (ref "R4") (pin "1") (pinfunction "1_1") (pintype "passive"))
      (node (ref "RJ1") (pin "TD+") (pinfunction "TD+_TD+") (pintype "bidirectional"))
    )
    (net (code "94") (name "TXD") (class "Default")
      (node (ref "IC3") (pin "48") (pinfunction "AETXD1/SCK1A/U1BTX/U1ARTS/CN21/BCLK1/RD15_48") (pintype "bidirectional"))
      (node (ref "JP3") (pin "2") (pinfunction "2_2") (pintype "passive"))
    )
    (net (code "95") (name "VBUS") (class "Default")
      (node (ref "C12") (pin "+") (pinfunction "+_+") (pintype "passive"))
      (node (ref "C13") (pin "1") (pinfunction "1_1") (pintype "passive"))
      (node (ref "C27") (pin "1") (pinfunction "1_1") (pintype "passive"))
      (node (ref "C30") (pin "+") (pinfunction "+_+") (pintype "passive"))
      (node (ref "C5") (pin "+") (pinfunction "+_+") (pintype "passive"))
      (node (ref "C52") (pin "+") (pinfunction "+_+") (pintype "passive"))
      (node (ref "C53") (pin "1") (pinfunction "1_1") (pintype "passive"))
      (node (ref "F1") (pin "2") (pinfunction "2_2") (pintype "passive"))
      (node (ref "IC1") (pin "5") (pinfunction "VBUS_5") (pintype "bidirectional"))
      (node (ref "IC2") (pin "3") (pinfunction "IN_3") (pintype "input"))
      (node (ref "IC3") (pin "54") (pinfunction "VBUS_54") (pintype "bidirectional"))
      (node (ref "IC5") (pin "3") (pinfunction "IN_3") (pintype "input"))
      (node (ref "SV1") (pin "31") (pinfunction "31_31") (pintype "passive"))
      (node (ref "SV1") (pin "32") (pinfunction "32_32") (pintype "passive"))
      (node (ref "X3") (pin "1") (pinfunction "1_1") (pintype "passive"))
    )
    (net (code "96") (name "VS_AGND") (class "Default")
      (node (ref "C33") (pin "2") (pinfunction "2_2") (pintype "passive"))
      (node (ref "C34") (pin "2") (pinfunction "2_2") (pintype "passive"))
      (node (ref "C35") (pin "2") (pinfunction "2_2") (pintype "passive"))
      (node (ref "C36") (pin "1") (pinfunction "1_1") (pintype "passive"))
      (node (ref "C37") (pin "1") (pinfunction "1_1") (pintype "passive"))
      (node (ref "C39") (pin "1") (pinfunction "1_1") (pintype "passive"))
      (node (ref "C58") (pin "2") (pinfunction "2_2") (pintype "passive"))
      (node (ref "JP1") (pin "SLEEVE") (pinfunction "SLEEVE_SLEEVE") (pintype "bidirectional"))
      (node (ref "R21") (pin "2") (pinfunction "2_2") (pintype "passive"))
      (node (ref "R25") (pin "1") (pinfunction "1_1") (pintype "passive"))
      (node (ref "R33") (pin "2") (pinfunction "2_2") (pintype "passive"))
      (node (ref "R34") (pin "2") (pinfunction "2_2") (pintype "passive"))
      (node (ref "U2") (pin "37") (pinfunction "AGND_37") (pintype "power_in"))
      (node (ref "U2") (pin "40") (pinfunction "AGND1_40") (pintype "power_in"))
      (node (ref "U2") (pin "41") (pinfunction "AGND2_41") (pintype "power_in"))
      (node (ref "U2") (pin "47") (pinfunction "AGND3_47") (pintype "power_in"))
    )
    (net (code "97") (name "VS_AVDD") (class "Default")
      (node (ref "C33") (pin "1") (pinfunction "1_1") (pintype "passive"))
      (node (ref "C34") (pin "1") (pinfunction "1_1") (pintype "passive"))
      (node (ref "C35") (pin "1") (pinfunction "1_1") (pintype "passive"))
      (node (ref "C58") (pin "1") (pinfunction "1_1") (pintype "passive"))
      (node (ref "L1") (pin "1") (pinfunction "1_1") (pintype "passive"))
      (node (ref "U2") (pin "38") (pinfunction "AVDD_38") (pintype "power_in"))
      (node (ref "U2") (pin "43") (pinfunction "AVDD1_43") (pintype "power_in"))
      (node (ref "U2") (pin "45") (pinfunction "AVDD2_45") (pintype "power_in"))
    )
    (net (code "98") (name "VS_CVDD") (class "Default")
      (node (ref "C45") (pin "1") (pinfunction "1_1") (pintype "passive"))
      (node (ref "C46") (pin "1") (pinfunction "1_1") (pintype "passive"))
      (node (ref "C47") (pin "1") (pinfunction "1_1") (pintype "passive"))
      (node (ref "C48") (pin "1") (pinfunction "1_1") (pintype "passive"))
      (node (ref "C57") (pin "1") (pinfunction "1_1") (pintype "passive"))
      (node (ref "L2") (pin "1") (pinfunction "1_1") (pintype "passive"))
      (node (ref "U2") (pin "24") (pinfunction "CVDD2_24") (pintype "power_in"))
      (node (ref "U2") (pin "31") (pinfunction "CVDD3_31") (pintype "power_in"))
      (node (ref "U2") (pin "5") (pinfunction "CVDD_5") (pintype "power_in"))
      (node (ref "U2") (pin "7") (pinfunction "CVDD1_7") (pintype "power_in"))
    )
    (net (code "99") (name "VS_DREQ") (class "Default")
      (node (ref "IC3") (pin "6") (pinfunction "RC1/T2CK_6") (pintype "bidirectional"))
      (node (ref "U2") (pin "8") (pinfunction "DREQ_8") (pintype "bidirectional"))
    )
    (net (code "100") (name "VS_MISO") (class "Default")
      (node (ref "IC3") (pin "9") (pinfunction "RC4/T5CK/SDI1_9") (pintype "bidirectional"))
      (node (ref "U2") (pin "30") (pinfunction "SO_30") (pintype "bidirectional"))
    )
    (net (code "101") (name "VS_MOSI") (class "Default")
      (node (ref "IC3") (pin "72") (pinfunction "SDO1/INT0/OC1/RD0_72") (pintype "bidirectional"))
      (node (ref "U2") (pin "29") (pinfunction "SI_29") (pintype "bidirectional"))
    )
    (net (code "102") (name "VS_SCK") (class "Default")
      (node (ref "IC3") (pin "70") (pinfunction "SCKI/IC3/PMCS2/PMA15/RD10_70") (pintype "bidirectional"))
      (node (ref "U2") (pin "28") (pinfunction "SCLK_28") (pintype "bidirectional"))
    )
    (net (code "103") (name "VS_XCS") (class "Default")
      (node (ref "IC3") (pin "5") (pinfunction "RE7/PMD7_5") (pintype "bidirectional"))
      (node (ref "U2") (pin "23") (pinfunction "XCS_23") (pintype "bidirectional"))
    )
    (net (code "104") (name "VS_XDCS") (class "Default")
      (node (ref "IC3") (pin "4") (pinfunction "RE6/PMD6_4") (pintype "bidirectional"))
      (node (ref "U2") (pin "13") (pinfunction "XDCS/BSYNC_13") (pintype "bidirectional"))
    )
    (net (code "105") (name "VS_XRST") (class "Default")
      (node (ref "IC3") (pin "7") (pinfunction "RC2/T3CK/AC2TX_7") (pintype "bidirectional"))
      (node (ref "R36") (pin "1") (pinfunction "1_1") (pintype "passive"))
      (node (ref "U2") (pin "3") (pinfunction "XRESET_3") (pintype "bidirectional"))
    )
    (net (code "106") (name "_2V6") (class "Default")
      (node (ref "C51") (pin "+") (pinfunction "+_+") (pintype "passive"))
      (node (ref "C54") (pin "1") (pinfunction "1_1") (pintype "passive"))
      (node (ref "IC5") (pin "2") (pinfunction "OUT_2") (pintype "passive"))
      (node (ref "IC5") (pin "TAB") (pinfunction "OUT1_TAB") (pintype "passive"))
      (node (ref "L1") (pin "2") (pinfunction "2_2") (pintype "passive"))
      (node (ref "L2") (pin "2") (pinfunction "2_2") (pintype "passive"))
    )
    (net (code "107") (name "unconnected-(IC3-AC1RX{slash}SS3A{slash}U3BRX{slash}U3ACTS{slash}RF12-Pad40)") (class "Default")
      (node (ref "IC3") (pin "40") (pinfunction "AC1RX/SS3A/U3BRX/U3ACTS/RF12_40") (pintype "bidirectional"))
    )
    (net (code "108") (name "unconnected-(IC3-ERXCLK{slash}SS2A{slash}U2BRX{slash}U2ACTS{slash}PMA2{slash}CN11{slash}RG9-Pad14)") (class "Default")
      (node (ref "IC3") (pin "14") (pinfunction "ERXCLK/SS2A/U2BRX/U2ACTS/PMA2/CN11/RG9_14") (pintype "bidirectional"))
    )
    (net (code "109") (name "unconnected-(IC3-RA0{slash}TMS-Pad17)") (class "Default")
      (node (ref "IC3") (pin "17") (pinfunction "RA0/TMS_17") (pintype "bidirectional"))
    )
    (net (code "110") (name "unconnected-(IC3-RA2{slash}SCL2-Pad58)") (class "Default")
      (node (ref "IC3") (pin "58") (pinfunction "RA2/SCL2_58") (pintype "bidirectional"))
    )
    (net (code "111") (name "unconnected-(IC3-RA3{slash}SDA2-Pad59)") (class "Default")
      (node (ref "IC3") (pin "59") (pinfunction "RA3/SDA2_59") (pintype "bidirectional"))
    )
    (net (code "112") (name "unconnected-(IC3-RA4{slash}TDI-Pad60)") (class "Default")
      (node (ref "IC3") (pin "60") (pinfunction "RA4/TDI_60") (pintype "bidirectional"))
    )
    (net (code "113") (name "unconnected-(IC3-RA5{slash}TDO-Pad61)") (class "Default")
      (node (ref "IC3") (pin "61") (pinfunction "RA5/TDO_61") (pintype "bidirectional"))
    )
    (net (code "114") (name "unconnected-(IC3-RA9{slash}VR-{slash}PMA7{slash}CVREF-{slash}AERXD2-Pad28)") (class "Default")
      (node (ref "IC3") (pin "28") (pinfunction "RA9/VR-/PMA7/CVREF-/AERXD2_28") (pintype "bidirectional"))
    )
    (net (code "115") (name "unconnected-(IC3-RA10{slash}VR+{slash}CVREF+{slash}AERXD3{slash}PMA6-Pad29)") (class "Default")
      (node (ref "IC3") (pin "29") (pinfunction "RA10/VR+/CVREF+/AERXD3/PMA6_29") (pintype "bidirectional"))
    )
    (net (code "116") (name "unconnected-(IC3-RB2{slash}AN2{slash}CN4{slash}C2IN--Pad23)") (class "Default")
      (node (ref "IC3") (pin "23") (pinfunction "RB2/AN2/CN4/C2IN-_23") (pintype "bidirectional"))
    )
    (net (code "117") (name "unconnected-(IC3-RB3{slash}AN3{slash}CN5{slash}C2IN+-Pad22)") (class "Default")
      (node (ref "IC3") (pin "22") (pinfunction "RB3/AN3/CN5/C2IN+_22") (pintype "bidirectional"))
    )
    (net (code "118") (name "unconnected-(IC3-RB4{slash}AN4{slash}CN6{slash}C1IN--Pad21)") (class "Default")
      (node (ref "IC3") (pin "21") (pinfunction "RB4/AN4/CN6/C1IN-_21") (pintype "bidirectional"))
    )
    (net (code "119") (name "unconnected-(IC3-RB5{slash}AN5{slash}CN7{slash}C1IN+{slash}VBUSON-Pad20)") (class "Default")
      (node (ref "IC3") (pin "20") (pinfunction "RB5/AN5/CN7/C1IN+/VBUSON_20") (pintype "bidirectional"))
    )
    (net (code "120") (name "unconnected-(IC3-RB6{slash}AN6{slash}PGC2{slash}OCFA-Pad26)") (class "Default")
      (node (ref "IC3") (pin "26") (pinfunction "RB6/AN6/PGC2/OCFA_26") (pintype "bidirectional"))
    )
    (net (code "121") (name "unconnected-(IC3-RB7{slash}AN7{slash}PGD2-Pad27)") (class "Default")
      (node (ref "IC3") (pin "27") (pinfunction "RB7/AN7/PGD2_27") (pintype "bidirectional"))
    )
    (net (code "122") (name "unconnected-(IC3-RB8{slash}AN8{slash}C1OUT-Pad32)") (class "Default")
      (node (ref "IC3") (pin "32") (pinfunction "RB8/AN8/C1OUT_32") (pintype "bidirectional"))
    )
    (net (code "123") (name "unconnected-(IC3-RB9{slash}AN9{slash}C2OUT-Pad33)") (class "Default")
      (node (ref "IC3") (pin "33") (pinfunction "RB9/AN9/C2OUT_33") (pintype "bidirectional"))
    )
    (net (code "124") (name "unconnected-(IC3-RB10{slash}AN10{slash}CVREF{slash}PMA13-Pad34)") (class "Default")
      (node (ref "IC3") (pin "34") (pinfunction "RB10/AN10/CVREF/PMA13_34") (pintype "bidirectional"))
    )
    (net (code "125") (name "unconnected-(IC3-RB11{slash}AN11{slash}PMA12{slash}ERXERR{slash}AETXERR-Pad35)") (class "Default")
      (node (ref "IC3") (pin "35") (pinfunction "RB11/AN11/PMA12/ERXERR/AETXERR_35") (pintype "bidirectional"))
    )
    (net (code "126") (name "unconnected-(IC3-RB12{slash}AN12{slash}PMA11{slash}ERXD0{slash}AECRS-Pad41)") (class "Default")
      (node (ref "IC3") (pin "41") (pinfunction "RB12/AN12/PMA11/ERXD0/AECRS_41") (pintype "bidirectional"))
    )
    (net (code "127") (name "unconnected-(IC3-RB13{slash}AN13{slash}PMA10{slash}ERXD1{slash}AECOL-Pad42)") (class "Default")
      (node (ref "IC3") (pin "42") (pinfunction "RB13/AN13/PMA10/ERXD1/AECOL_42") (pintype "bidirectional"))
    )
    (net (code "128") (name "unconnected-(IC3-RB14{slash}AN14{slash}PMA1{slash}ERXD2{slash}AETXD3{slash}-Pad43)") (class "Default")
      (node (ref "IC3") (pin "43") (pinfunction "RB14/AN14/PMA1/ERXD2/AETXD3/_43") (pintype "bidirectional"))
    )
    (net (code "129") (name "unconnected-(IC3-RB15{slash}AN15{slash}CN12{slash}OCFB{slash}-Pad44)") (class "Default")
      (node (ref "IC3") (pin "44") (pinfunction "RB15/AN15/CN12/OCFB/_44") (pintype "bidirectional"))
    )
    (net (code "130") (name "unconnected-(IC3-RE8{slash}INT1{slash}AERXD0-Pad18)") (class "Default")
      (node (ref "IC3") (pin "18") (pinfunction "RE8/INT1/AERXD0_18") (pintype "bidirectional"))
    )
    (net (code "131") (name "unconnected-(IC3-RE9{slash}INT2{slash}AERXD1-Pad19)") (class "Default")
      (node (ref "IC3") (pin "19") (pinfunction "RE9/INT2/AERXD1_19") (pintype "bidirectional"))
    )
    (net (code "132") (name "unconnected-(IC4-CLKOUT-PadP$3)") (class "Default")
      (node (ref "IC4") (pin "P$3") (pinfunction "CLKOUT_P$3") (pintype "output"))
    )
    (net (code "133") (name "unconnected-(IC4-NC*-PadP$5)") (class "Default")
      (node (ref "IC4") (pin "P$5") (pinfunction "NC*_P$5") (pintype "output"))
    )
    (net (code "134") (name "unconnected-(IC4-~{INT}-PadP$4)") (class "Default")
      (node (ref "IC4") (pin "P$4") (pinfunction "~{INT}_P$4") (pintype "output"))
    )
    (net (code "135") (name "unconnected-(JP2-Pad2)") (class "Default")
      (node (ref "JP2") (pin "2") (pinfunction "2_2") (pintype "passive"))
    )
    (net (code "136") (name "unconnected-(JP2-Pad6)") (class "Default")
      (node (ref "JP2") (pin "6") (pinfunction "6_6") (pintype "passive"))
    )
    (net (code "137") (name "unconnected-(JP5-D+-PadD+1)") (class "Default")
      (node (ref "JP5") (pin "D+1") (pinfunction "D+_D+1") (pintype "bidirectional"))
    )
    (net (code "138") (name "unconnected-(JP5-D--PadD-1)") (class "Default")
      (node (ref "JP5") (pin "D-1") (pinfunction "D-_D-1") (pintype "bidirectional"))
    )
    (net (code "139") (name "unconnected-(JP5-ID-PadID1)") (class "Default")
      (node (ref "JP5") (pin "ID1") (pinfunction "ID_ID1") (pintype "bidirectional"))
    )
    (net (code "140") (name "unconnected-(RJ1-PadNC)") (class "Default")
      (node (ref "RJ1") (pin "NC") (pinfunction "NC_NC") (pintype "bidirectional"))
    )
    (net (code "141") (name "unconnected-(RJ1-PadP5)") (class "Default")
      (node (ref "RJ1") (pin "P5") (pinfunction "P5_P5") (pintype "bidirectional"))
    )
    (net (code "142") (name "unconnected-(U1-NC-Pad1)") (class "Default")
      (node (ref "U1") (pin "1") (pinfunction "NC_1") (pintype "bidirectional"))
    )
    (net (code "143") (name "unconnected-(U1-RSV-Pad8)") (class "Default")
      (node (ref "U1") (pin "8") (pinfunction "RSV_8") (pintype "bidirectional"))
    )
    (net (code "144") (name "unconnected-(U2A-LINEIN-Pad48)") (class "Default")
      (node (ref "U2") (pin "48") (pinfunction "LINEIN_48") (pintype "bidirectional"))
    )
    (net (code "145") (name "unconnected-(U2A-MICN-Pad2)") (class "Default")
      (node (ref "U2") (pin "2") (pinfunction "MICN_2") (pintype "bidirectional"))
    )
    (net (code "146") (name "unconnected-(U2A-MICP-Pad1)") (class "Default")
      (node (ref "U2") (pin "1") (pinfunction "MICP_1") (pintype "bidirectional"))
    )
    (net (code "147") (name "unconnected-(U2A-TX-Pad27)") (class "Default")
      (node (ref "U2") (pin "27") (pinfunction "TX_27") (pintype "bidirectional"))
    )
    (net (code "148") (name "unconnected-(U2A-VCO-Pad15)") (class "Default")
      (node (ref "U2") (pin "15") (pinfunction "VCO_15") (pintype "bidirectional"))
    )
  )
)
